# first_board5.net
KiCad netlist of a schematic drawn in EAGLE
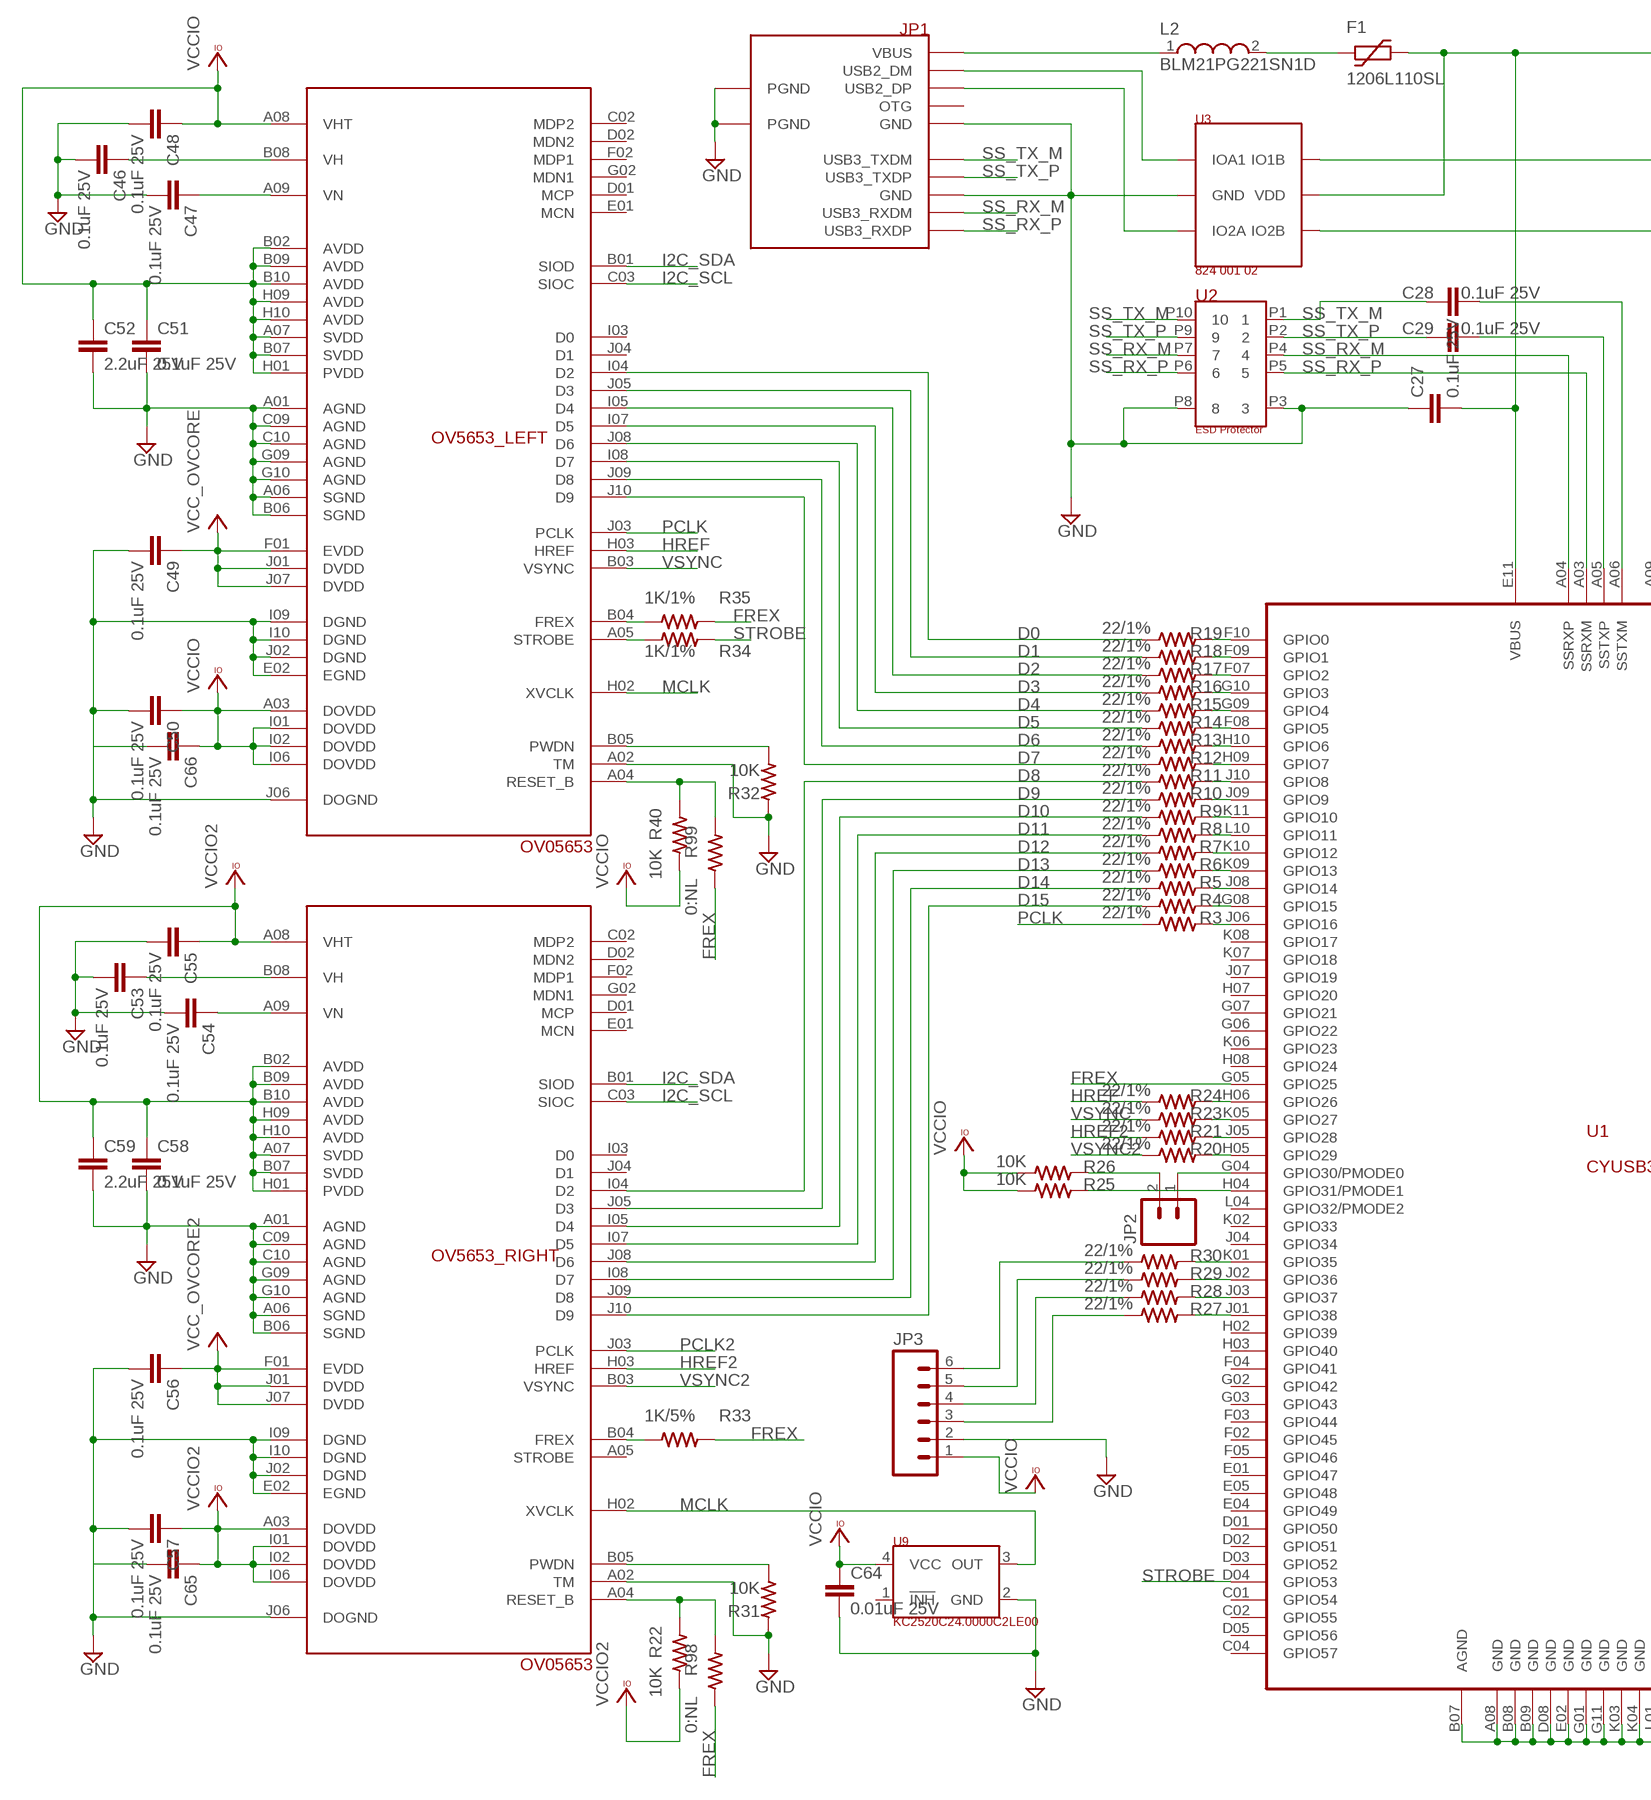
[diagram p0: schematic, sheet 1, part 1 of 2]
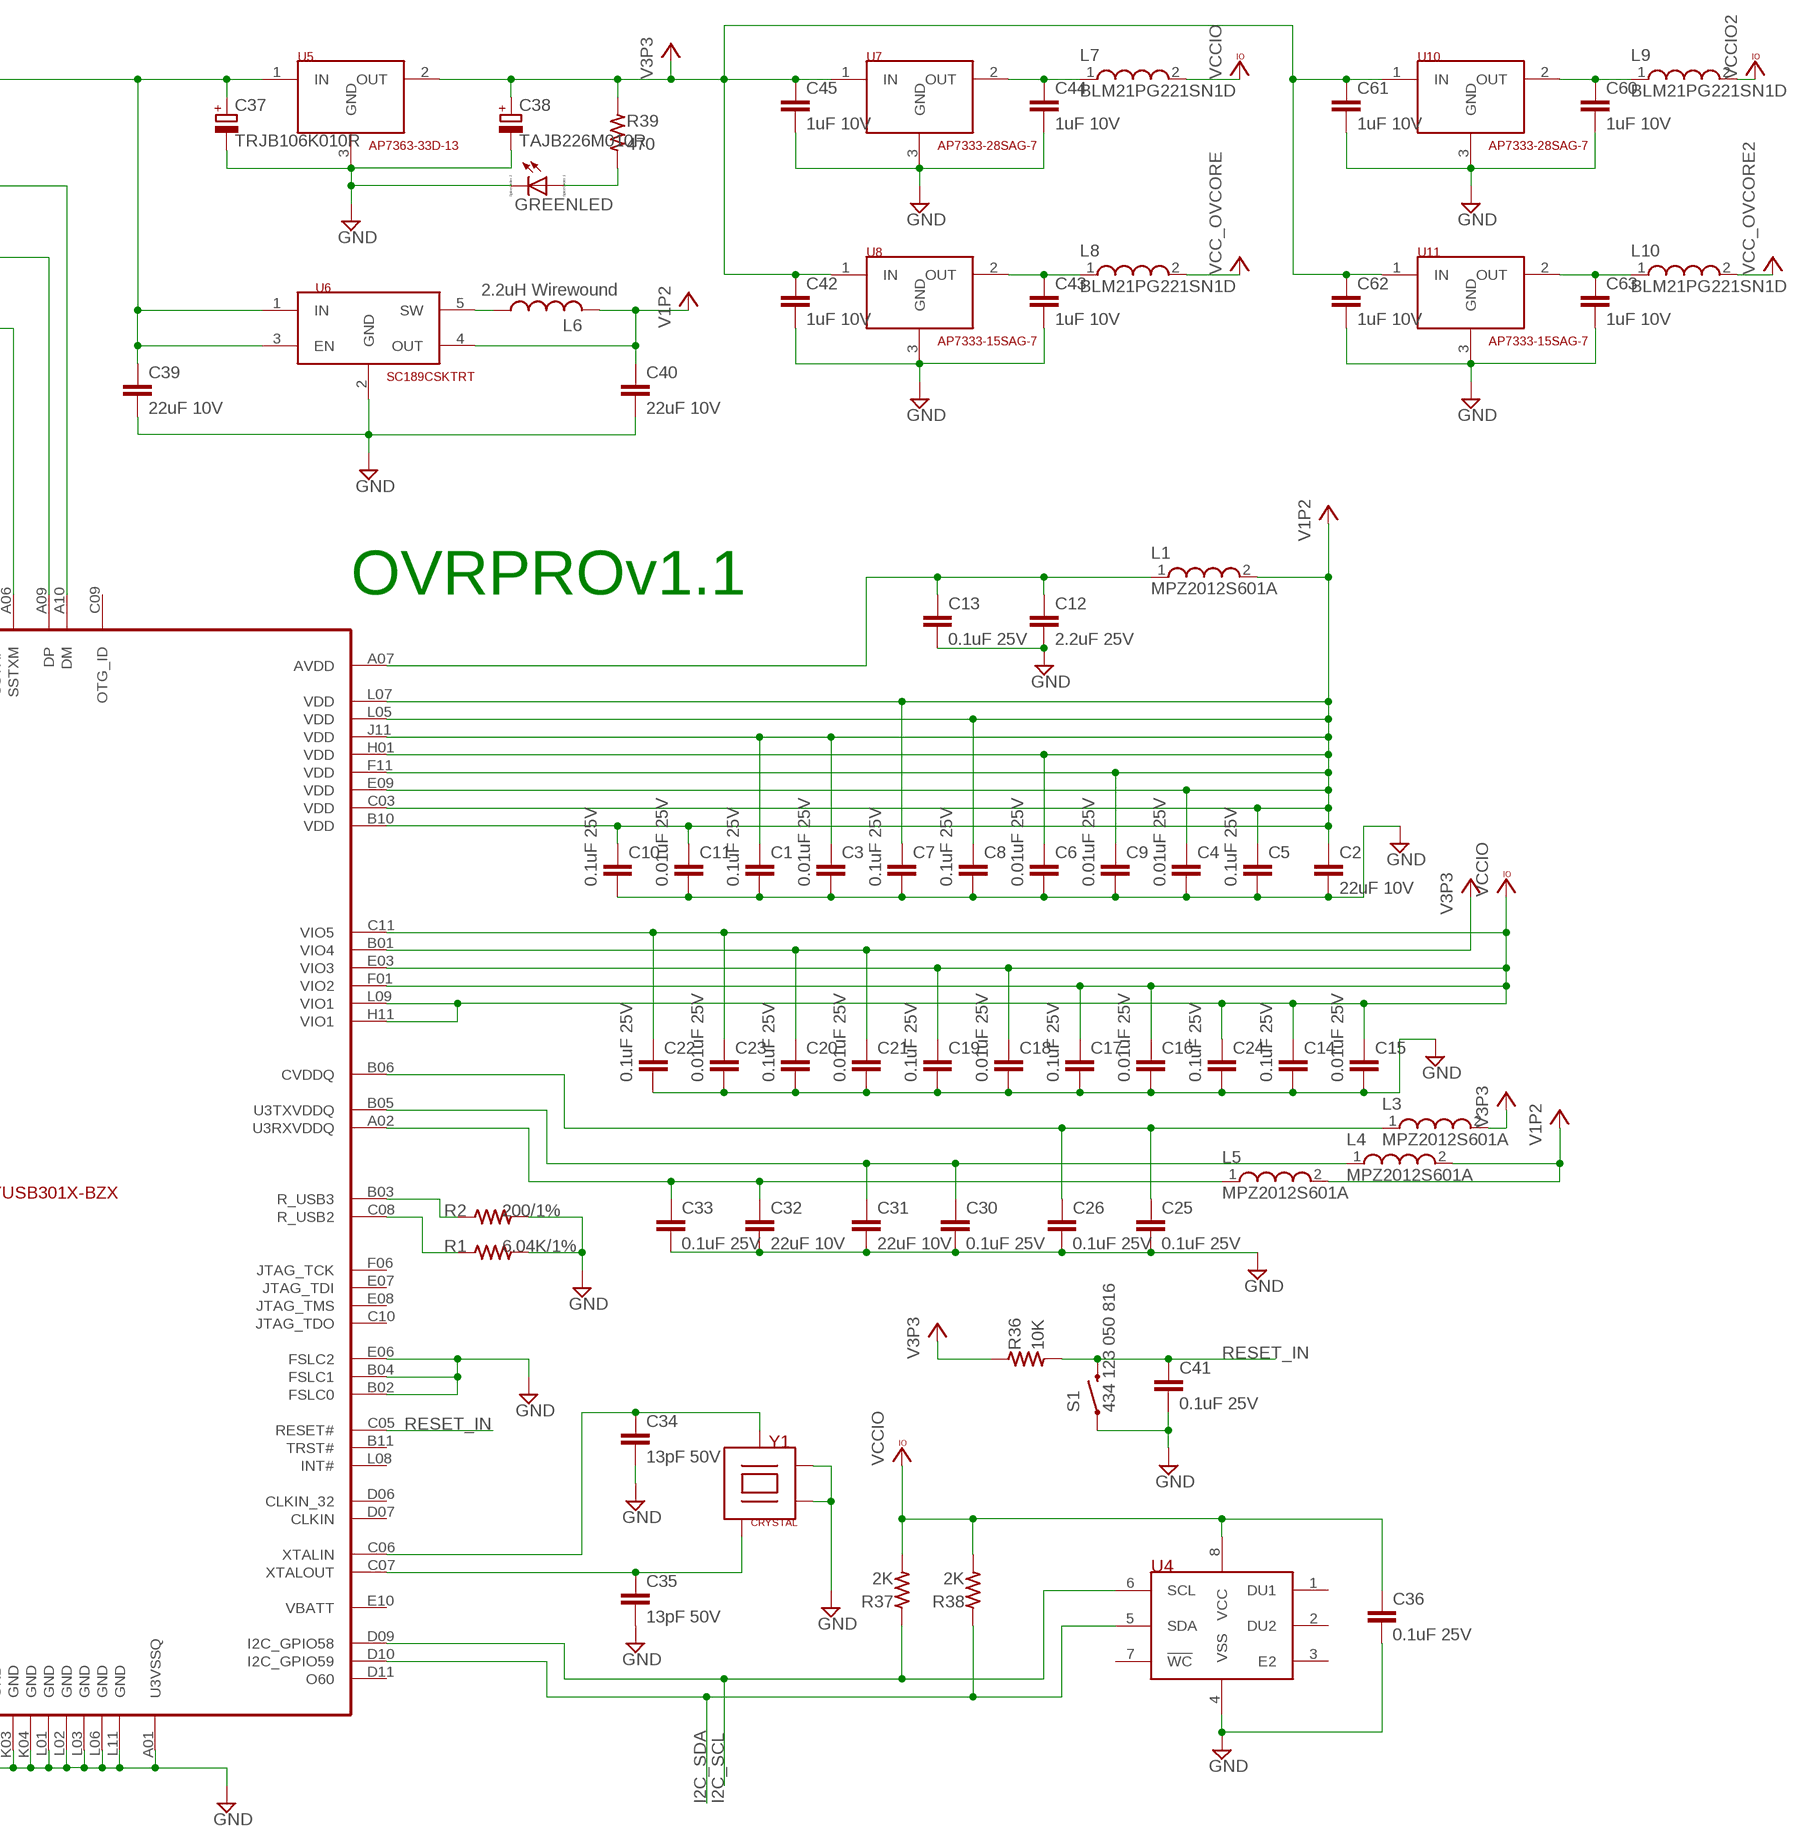
[diagram p1: schematic, sheet 1, part 2 of 2]

(export (version "E")
  (design (tool "Eeschema 10.0.6"))
  (components
    (comp (ref "C1")
      (value "0.1uF 25V")
      (footprint "eagle-import:C0402K")
      (libsource (lib "eagle-import") (part "C-EUC0402K"))
    )
    (comp (ref "C2")
      (value "22uF 10V")
      (footprint "eagle-import:C1206")
      (libsource (lib "eagle-import") (part "C-EUC1206"))
    )
    (comp (ref "C3")
      (value "0.01uF 25V")
      (footprint "eagle-import:C0402K")
      (libsource (lib "eagle-import") (part "C-EUC0402K"))
    )
    (comp (ref "C4")
      (value "0.01uF 25V")
      (footprint "eagle-import:C0402K")
      (libsource (lib "eagle-import") (part "C-EUC0402K"))
    )
    (comp (ref "C5")
      (value "0.1uF 25V")
      (footprint "eagle-import:C0402K")
      (libsource (lib "eagle-import") (part "C-EUC0402K"))
    )
    (comp (ref "C6")
      (value "0.01uF 25V")
      (footprint "eagle-import:C0402K")
      (libsource (lib "eagle-import") (part "C-EUC0402K"))
    )
    (comp (ref "C7")
      (value "0.1uF 25V")
      (footprint "eagle-import:C0402K")
      (libsource (lib "eagle-import") (part "C-EUC0402K"))
    )
    (comp (ref "C8")
      (value "0.1uF 25V")
      (footprint "eagle-import:C0402K")
      (libsource (lib "eagle-import") (part "C-EUC0402K"))
    )
    (comp (ref "C9")
      (value "0.01uF 25V")
      (footprint "eagle-import:C0402K")
      (libsource (lib "eagle-import") (part "C-EUC0402K"))
    )
    (comp (ref "C10")
      (value "0.1uF 25V")
      (footprint "eagle-import:C0402K")
      (libsource (lib "eagle-import") (part "C-EUC0402K"))
    )
    (comp (ref "C11")
      (value "0.01uF 25V")
      (footprint "eagle-import:C0402K")
      (libsource (lib "eagle-import") (part "C-EUC0402K"))
    )
    (comp (ref "C12")
      (value "2.2uF 25V")
      (footprint "eagle-import:C0805")
      (libsource (lib "eagle-import") (part "C-EUC0805"))
    )
    (comp (ref "C13")
      (value "0.1uF 25V")
      (footprint "eagle-import:C0402K")
      (libsource (lib "eagle-import") (part "C-EUC0402K"))
    )
    (comp (ref "C14")
      (value "0.1uF 25V")
      (footprint "eagle-import:C0402K")
      (libsource (lib "eagle-import") (part "C-EUC0402K"))
    )
    (comp (ref "C15")
      (value "0.01uF 25V")
      (footprint "eagle-import:C0402K")
      (libsource (lib "eagle-import") (part "C-EUC0402K"))
    )
    (comp (ref "C16")
      (value "0.01uF 25V")
      (footprint "eagle-import:C0402K")
      (libsource (lib "eagle-import") (part "C-EUC0402K"))
    )
    (comp (ref "C17")
      (value "0.1uF 25V")
      (footprint "eagle-import:C0402K")
      (libsource (lib "eagle-import") (part "C-EUC0402K"))
    )
    (comp (ref "C18")
      (value "0.01uF 25V")
      (footprint "eagle-import:C0402K")
      (libsource (lib "eagle-import") (part "C-EUC0402K"))
    )
    (comp (ref "C19")
      (value "0.1uF 25V")
      (footprint "eagle-import:C0402K")
      (libsource (lib "eagle-import") (part "C-EUC0402K"))
    )
    (comp (ref "C20")
      (value "0.1uF 25V")
      (footprint "eagle-import:C0402K")
      (libsource (lib "eagle-import") (part "C-EUC0402K"))
    )
    (comp (ref "C21")
      (value "0.01uF 25V")
      (footprint "eagle-import:C0402K")
      (libsource (lib "eagle-import") (part "C-EUC0402K"))
    )
    (comp (ref "C22")
      (value "0.1uF 25V")
      (footprint "eagle-import:C0402K")
      (libsource (lib "eagle-import") (part "C-EUC0402K"))
    )
    (comp (ref "C23")
      (value "0.01uF 25V")
      (footprint "eagle-import:C0402K")
      (libsource (lib "eagle-import") (part "C-EUC0402K"))
    )
    (comp (ref "C24")
      (value "0.1uF 25V")
      (footprint "eagle-import:C0402")
      (libsource (lib "eagle-import") (part "C-EUC0402"))
    )
    (comp (ref "C25")
      (value "0.1uF 25V")
      (footprint "eagle-import:C0402K")
      (libsource (lib "eagle-import") (part "C-EUC0402K"))
    )
    (comp (ref "C26")
      (value "0.1uF 25V")
      (footprint "eagle-import:C0402K")
      (libsource (lib "eagle-import") (part "C-EUC0402K"))
    )
    (comp (ref "C27")
      (value "0.1uF 25V")
      (footprint "eagle-import:C0402K")
      (libsource (lib "eagle-import") (part "C-EUC0402K"))
    )
    (comp (ref "C28")
      (value "0.1uF 25V")
      (footprint "eagle-import:C0402K")
      (libsource (lib "eagle-import") (part "C-EUC0402K"))
    )
    (comp (ref "C29")
      (value "0.1uF 25V")
      (footprint "eagle-import:C0402K")
      (libsource (lib "eagle-import") (part "C-EUC0402K"))
    )
    (comp (ref "C30")
      (value "0.1uF 25V")
      (footprint "eagle-import:C0402K")
      (libsource (lib "eagle-import") (part "C-EUC0402K"))
    )
    (comp (ref "C31")
      (value "22uF 10V")
      (footprint "eagle-import:C1206")
      (libsource (lib "eagle-import") (part "C-EUC1206"))
    )
    (comp (ref "C32")
      (value "22uF 10V")
      (footprint "eagle-import:C1206")
      (libsource (lib "eagle-import") (part "C-EUC1206"))
    )
    (comp (ref "C33")
      (value "0.1uF 25V")
      (footprint "eagle-import:C0402K")
      (libsource (lib "eagle-import") (part "C-EUC0402K"))
    )
    (comp (ref "C34")
      (value "13pF 50V")
      (footprint "eagle-import:C0402K")
      (libsource (lib "eagle-import") (part "C-EUC0402K"))
    )
    (comp (ref "C35")
      (value "13pF 50V")
      (footprint "eagle-import:C0402K")
      (libsource (lib "eagle-import") (part "C-EUC0402K"))
    )
    (comp (ref "C36")
      (value "0.1uF 25V")
      (footprint "eagle-import:C0402")
      (libsource (lib "eagle-import") (part "C-EUC0402"))
    )
    (comp (ref "C37")
      (value "TRJB106K010R")
      (footprint "eagle-import:CT3528")
      (libsource (lib "eagle-import") (part "CPOL-EUCT3528"))
    )
    (comp (ref "C38")
      (value "TAJB226M010R")
      (footprint "eagle-import:CT3528")
      (libsource (lib "eagle-import") (part "CPOL-EUCT3528"))
    )
    (comp (ref "C39")
      (value "22uF 10V")
      (footprint "eagle-import:C1206")
      (libsource (lib "eagle-import") (part "C-EUC1206"))
    )
    (comp (ref "C40")
      (value "22uF 10V")
      (footprint "eagle-import:C1206")
      (libsource (lib "eagle-import") (part "C-EUC1206"))
    )
    (comp (ref "C41")
      (value "0.1uF 25V")
      (footprint "eagle-import:C0402")
      (libsource (lib "eagle-import") (part "C-EUC0402"))
    )
    (comp (ref "C42")
      (value "1uF 10V")
      (footprint "eagle-import:C0402")
      (libsource (lib "eagle-import") (part "C-EUC0402"))
    )
    (comp (ref "C43")
      (value "1uF 10V")
      (footprint "eagle-import:C0402")
      (libsource (lib "eagle-import") (part "C-EUC0402"))
    )
    (comp (ref "C44")
      (value "1uF 10V")
      (footprint "eagle-import:C0402")
      (libsource (lib "eagle-import") (part "C-EUC0402"))
    )
    (comp (ref "C45")
      (value "1uF 10V")
      (footprint "eagle-import:C0402")
      (libsource (lib "eagle-import") (part "C-EUC0402"))
    )
    (comp (ref "C46")
      (value "0.1uF 25V")
      (footprint "eagle-import:C0402K")
      (libsource (lib "eagle-import") (part "C-EUC0402K"))
    )
    (comp (ref "C47")
      (value "0.1uF 25V")
      (footprint "eagle-import:C0402K")
      (libsource (lib "eagle-import") (part "C-EUC0402K"))
    )
    (comp (ref "C48")
      (value "0.1uF 25V")
      (footprint "eagle-import:C0402K")
      (libsource (lib "eagle-import") (part "C-EUC0402K"))
    )
    (comp (ref "C49")
      (value "0.1uF 25V")
      (footprint "eagle-import:C0402K")
      (libsource (lib "eagle-import") (part "C-EUC0402K"))
    )
    (comp (ref "C50")
      (value "0.1uF 25V")
      (footprint "eagle-import:C0402K")
      (libsource (lib "eagle-import") (part "C-EUC0402K"))
    )
    (comp (ref "C51")
      (value "0.1uF 25V")
      (footprint "eagle-import:C0402K")
      (libsource (lib "eagle-import") (part "C-EUC0402K"))
    )
    (comp (ref "C52")
      (value "2.2uF 25V")
      (footprint "eagle-import:C0805")
      (libsource (lib "eagle-import") (part "C-EUC0805"))
    )
    (comp (ref "C53")
      (value "0.1uF 25V")
      (footprint "eagle-import:C0402K")
      (libsource (lib "eagle-import") (part "C-EUC0402K"))
    )
    (comp (ref "C54")
      (value "0.1uF 25V")
      (footprint "eagle-import:C0402K")
      (libsource (lib "eagle-import") (part "C-EUC0402K"))
    )
    (comp (ref "C55")
      (value "0.1uF 25V")
      (footprint "eagle-import:C0402K")
      (libsource (lib "eagle-import") (part "C-EUC0402K"))
    )
    (comp (ref "C56")
      (value "0.1uF 25V")
      (footprint "eagle-import:C0402K")
      (libsource (lib "eagle-import") (part "C-EUC0402K"))
    )
    (comp (ref "C57")
      (value "0.1uF 25V")
      (footprint "eagle-import:C0402K")
      (libsource (lib "eagle-import") (part "C-EUC0402K"))
    )
    (comp (ref "C58")
      (value "0.1uF 25V")
      (footprint "eagle-import:C0402K")
      (libsource (lib "eagle-import") (part "C-EUC0402K"))
    )
    (comp (ref "C59")
      (value "2.2uF 25V")
      (footprint "eagle-import:C0805")
      (libsource (lib "eagle-import") (part "C-EUC0805"))
    )
    (comp (ref "C60")
      (value "1uF 10V")
      (footprint "eagle-import:C0402")
      (libsource (lib "eagle-import") (part "C-EUC0402"))
    )
    (comp (ref "C61")
      (value "1uF 10V")
      (footprint "eagle-import:C0402")
      (libsource (lib "eagle-import") (part "C-EUC0402"))
    )
    (comp (ref "C62")
      (value "1uF 10V")
      (footprint "eagle-import:C0402")
      (libsource (lib "eagle-import") (part "C-EUC0402"))
    )
    (comp (ref "C63")
      (value "1uF 10V")
      (footprint "eagle-import:C0402")
      (libsource (lib "eagle-import") (part "C-EUC0402"))
    )
    (comp (ref "C64")
      (value "0.01uF 25V")
      (footprint "eagle-import:C0402K")
      (libsource (lib "eagle-import") (part "C-EUC0402K"))
    )
    (comp (ref "C65")
      (value "0.1uF 25V")
      (footprint "eagle-import:C0402K")
      (libsource (lib "eagle-import") (part "C-EUC0402K"))
    )
    (comp (ref "C66")
      (value "0.1uF 25V")
      (footprint "eagle-import:C0402K")
      (libsource (lib "eagle-import") (part "C-EUC0402K"))
    )
    (comp (ref "F1")
      (value "1206L110SL")
      (footprint "eagle-import:1206L")
      (libsource (lib "eagle-import") (part "1206L"))
    )
    (comp (ref "GREENLED")
      (value "LED_ESML0603")
      (footprint "eagle-import:LED_SML0603")
      (libsource (lib "eagle-import") (part "LED_ESML0603"))
    )
    (comp (ref "JP1")
      (value "ZX360D-B-10PUSB3")
      (footprint "eagle-import:ZX360D-B-10PUSB3")
      (libsource (lib "eagle-import") (part "ZX360D-B-10PUSB3"))
    )
    (comp (ref "JP2")
      (value "M02PTH")
      (footprint "eagle-import:1X02")
      (libsource (lib "eagle-import") (part "M02PTH"))
    )
    (comp (ref "JP3")
      (value "M06SILK_FEMALE_PTH")
      (footprint "eagle-import:1X06")
      (libsource (lib "eagle-import") (part "M06SILK_FEMALE_PTH"))
    )
    (comp (ref "L1")
      (value "MPZ2012S601A")
      (footprint "eagle-import:WE-CBA_0805(W=3)")
      (libsource (lib "eagle-import") (part "WE-CBA_0805(WB/HS)"))
    )
    (comp (ref "L2")
      (value "BLM21PG221SN1D")
      (footprint "eagle-import:WE-CBA_0805(W=3)")
      (libsource (lib "eagle-import") (part "WE-CBA_0805(WB/HS)"))
    )
    (comp (ref "L3")
      (value "MPZ2012S601A")
      (footprint "eagle-import:WE-CBA_0805(W=3)")
      (libsource (lib "eagle-import") (part "WE-CBA_0805(WB/HS)"))
    )
    (comp (ref "L4")
      (value "MPZ2012S601A")
      (footprint "eagle-import:WE-CBA_0805(W=3)")
      (libsource (lib "eagle-import") (part "WE-CBA_0805(WB/HS)"))
    )
    (comp (ref "L5")
      (value "MPZ2012S601A")
      (footprint "eagle-import:WE-CBA_0805(W=3)")
      (libsource (lib "eagle-import") (part "WE-CBA_0805(WB/HS)"))
    )
    (comp (ref "L6")
      (value "2.2uH Wirewound")
      (footprint "eagle-import:L3225M")
      (libsource (lib "eagle-import") (part "L-USL3225M"))
    )
    (comp (ref "L7")
      (value "BLM21PG221SN1D")
      (footprint "eagle-import:WE-CBA_0805(W=3)")
      (libsource (lib "eagle-import") (part "WE-CBA_0805(WB/HS)"))
    )
    (comp (ref "L8")
      (value "BLM21PG221SN1D")
      (footprint "eagle-import:WE-CBA_0805(W=3)")
      (libsource (lib "eagle-import") (part "WE-CBA_0805(WB/HS)"))
    )
    (comp (ref "L9")
      (value "BLM21PG221SN1D")
      (footprint "eagle-import:WE-CBA_0805(W=3)")
      (libsource (lib "eagle-import") (part "WE-CBA_0805(WB/HS)"))
    )
    (comp (ref "L10")
      (value "BLM21PG221SN1D")
      (footprint "eagle-import:WE-CBA_0805(W=3)")
      (libsource (lib "eagle-import") (part "WE-CBA_0805(WB/HS)"))
    )
    (comp (ref "OV5653_LEFT")
      (value "OV05653-A66A")
      (footprint "eagle-import:OV05653-A66A")
      (libsource (lib "eagle-import") (part "OV05653-A66A"))
    )
    (comp (ref "OV5653_RIGHT")
      (value "OV05653-A66A")
      (footprint "eagle-import:OV05653-A66A")
      (libsource (lib "eagle-import") (part "OV05653-A66A"))
    )
    (comp (ref "R1")
      (value "6.04K/1%")
      (footprint "eagle-import:SMD1608")
      (libsource (lib "eagle-import") (part "RESISTOR-US1608"))
    )
    (comp (ref "R2")
      (value "200/1%")
      (footprint "eagle-import:SMD1608")
      (libsource (lib "eagle-import") (part "RESISTOR-US1608"))
    )
    (comp (ref "R3")
      (value "22/1%")
      (footprint "eagle-import:SMD1005")
      (libsource (lib "eagle-import") (part "RESISTOR-US1005"))
    )
    (comp (ref "R4")
      (value "22/1%")
      (footprint "eagle-import:SMD1005")
      (libsource (lib "eagle-import") (part "RESISTOR-US1005"))
    )
    (comp (ref "R5")
      (value "22/1%")
      (footprint "eagle-import:SMD1005")
      (libsource (lib "eagle-import") (part "RESISTOR-US1005"))
    )
    (comp (ref "R6")
      (value "22/1%")
      (footprint "eagle-import:SMD1005")
      (libsource (lib "eagle-import") (part "RESISTOR-US1005"))
    )
    (comp (ref "R7")
      (value "22/1%")
      (footprint "eagle-import:SMD1005")
      (libsource (lib "eagle-import") (part "RESISTOR-US1005"))
    )
    (comp (ref "R8")
      (value "22/1%")
      (footprint "eagle-import:SMD1005")
      (libsource (lib "eagle-import") (part "RESISTOR-US1005"))
    )
    (comp (ref "R9")
      (value "22/1%")
      (footprint "eagle-import:SMD1005")
      (libsource (lib "eagle-import") (part "RESISTOR-US1005"))
    )
    (comp (ref "R10")
      (value "22/1%")
      (footprint "eagle-import:SMD1005")
      (libsource (lib "eagle-import") (part "RESISTOR-US1005"))
    )
    (comp (ref "R11")
      (value "22/1%")
      (footprint "eagle-import:SMD1005")
      (libsource (lib "eagle-import") (part "RESISTOR-US1005"))
    )
    (comp (ref "R12")
      (value "22/1%")
      (footprint "eagle-import:SMD1005")
      (libsource (lib "eagle-import") (part "RESISTOR-US1005"))
    )
    (comp (ref "R13")
      (value "22/1%")
      (footprint "eagle-import:SMD1005")
      (libsource (lib "eagle-import") (part "RESISTOR-US1005"))
    )
    (comp (ref "R14")
      (value "22/1%")
      (footprint "eagle-import:SMD1005")
      (libsource (lib "eagle-import") (part "RESISTOR-US1005"))
    )
    (comp (ref "R15")
      (value "22/1%")
      (footprint "eagle-import:SMD1005")
      (libsource (lib "eagle-import") (part "RESISTOR-US1005"))
    )
    (comp (ref "R16")
      (value "22/1%")
      (footprint "eagle-import:SMD1005")
      (libsource (lib "eagle-import") (part "RESISTOR-US1005"))
    )
    (comp (ref "R17")
      (value "22/1%")
      (footprint "eagle-import:SMD1005")
      (libsource (lib "eagle-import") (part "RESISTOR-US1005"))
    )
    (comp (ref "R18")
      (value "22/1%")
      (footprint "eagle-import:SMD1005")
      (libsource (lib "eagle-import") (part "RESISTOR-US1005"))
    )
    (comp (ref "R19")
      (value "22/1%")
      (footprint "eagle-import:SMD1005")
      (libsource (lib "eagle-import") (part "RESISTOR-US1005"))
    )
    (comp (ref "R20")
      (value "22/1%")
      (footprint "eagle-import:SMD1005")
      (libsource (lib "eagle-import") (part "RESISTOR-US1005"))
    )
    (comp (ref "R21")
      (value "22/1%")
      (footprint "eagle-import:SMD1005")
      (libsource (lib "eagle-import") (part "RESISTOR-US1005"))
    )
    (comp (ref "R22")
      (value "10K")
      (footprint "eagle-import:SMD1608")
      (libsource (lib "eagle-import") (part "RESISTOR-US1608"))
    )
    (comp (ref "R23")
      (value "22/1%")
      (footprint "eagle-import:SMD1005")
      (libsource (lib "eagle-import") (part "RESISTOR-US1005"))
    )
    (comp (ref "R24")
      (value "22/1%")
      (footprint "eagle-import:SMD1005")
      (libsource (lib "eagle-import") (part "RESISTOR-US1005"))
    )
    (comp (ref "R25")
      (value "10K")
      (footprint "eagle-import:SMD1608")
      (libsource (lib "eagle-import") (part "RESISTOR-US1608"))
    )
    (comp (ref "R26")
      (value "10K")
      (footprint "eagle-import:SMD1608")
      (libsource (lib "eagle-import") (part "RESISTOR-US1608"))
    )
    (comp (ref "R27")
      (value "22/1%")
      (footprint "eagle-import:SMD1005")
      (libsource (lib "eagle-import") (part "RESISTOR-US1005"))
    )
    (comp (ref "R28")
      (value "22/1%")
      (footprint "eagle-import:SMD1005")
      (libsource (lib "eagle-import") (part "RESISTOR-US1005"))
    )
    (comp (ref "R29")
      (value "22/1%")
      (footprint "eagle-import:SMD1005")
      (libsource (lib "eagle-import") (part "RESISTOR-US1005"))
    )
    (comp (ref "R30")
      (value "22/1%")
      (footprint "eagle-import:SMD1005")
      (libsource (lib "eagle-import") (part "RESISTOR-US1005"))
    )
    (comp (ref "R31")
      (value "10K")
      (footprint "eagle-import:SMD1608")
      (libsource (lib "eagle-import") (part "RESISTOR-US1608"))
    )
    (comp (ref "R32")
      (value "10K")
      (footprint "eagle-import:SMD1608")
      (libsource (lib "eagle-import") (part "RESISTOR-US1608"))
    )
    (comp (ref "R33")
      (value "1K/5%")
      (footprint "eagle-import:SMD1005")
      (libsource (lib "eagle-import") (part "RESISTOR-US1005"))
    )
    (comp (ref "R34")
      (value "1K/1%")
      (footprint "eagle-import:SMD1005")
      (libsource (lib "eagle-import") (part "RESISTOR-US1005"))
    )
    (comp (ref "R35")
      (value "1K/1%")
      (footprint "eagle-import:SMD1005")
      (libsource (lib "eagle-import") (part "RESISTOR-US1005"))
    )
    (comp (ref "R36")
      (value "10K")
      (footprint "eagle-import:SMD1608")
      (libsource (lib "eagle-import") (part "RESISTOR-US1608"))
    )
    (comp (ref "R37")
      (value "2K")
      (footprint "eagle-import:SMD1608")
      (libsource (lib "eagle-import") (part "RESISTOR-US1608"))
    )
    (comp (ref "R38")
      (value "2K")
      (footprint "eagle-import:SMD1608")
      (libsource (lib "eagle-import") (part "RESISTOR-US1608"))
    )
    (comp (ref "R39")
      (value "470")
      (footprint "eagle-import:SMD1608")
      (libsource (lib "eagle-import") (part "RESISTOR-US1608"))
    )
    (comp (ref "R40")
      (value "10K")
      (footprint "eagle-import:SMD1608")
      (libsource (lib "eagle-import") (part "RESISTOR-US1608"))
    )
    (comp (ref "R98")
      (value "0:NL")
      (footprint "eagle-import:SMD1005")
      (libsource (lib "eagle-import") (part "RESISTOR-US1005"))
    )
    (comp (ref "R99")
      (value "0:NL")
      (footprint "eagle-import:SMD1005")
      (libsource (lib "eagle-import") (part "RESISTOR-US1005"))
    )
    (comp (ref "S1")
      (value "434 123 050 816")
      (footprint "eagle-import:TACTILE-SWITCH-1101NE")
      (libsource (lib "eagle-import") (part "SWITCH-MOMENTARY-2SMD-1101NE"))
    )
    (comp (ref "U1")
      (value "CYUSB301X-BZX")
      (footprint "eagle-import:BGA121")
      (libsource (lib "eagle-import") (part "CYUSB301X-BZX"))
    )
    (comp (ref "U2")
      (value "SP3010-04UTG")
      (footprint "eagle-import:SP3010-04UTG")
      (libsource (lib "eagle-import") (part "SP3010-04UTG"))
    )
    (comp (ref "U3")
      (value "WE-82400102")
      (footprint "eagle-import:WE-82400102")
      (libsource (lib "eagle-import") (part "WE-82400102"))
    )
    (comp (ref "U4")
      (value "M24M02-DRMN6TP")
      (footprint "eagle-import:SO-08")
      (libsource (lib "eagle-import") (part "M24M02-DRMN6TP"))
    )
    (comp (ref "U5")
      (value "AP7363-33D-13")
      (footprint "eagle-import:TO-252")
      (libsource (lib "eagle-import") (part "AP7363-XXD-13"))
    )
    (comp (ref "U6")
      (value "SC189CSKTRT")
      (footprint "eagle-import:SOT23-5")
      (libsource (lib "eagle-import") (part "PAM2305AABXXX"))
    )
    (comp (ref "U7")
      (value "AP7333-28SAG-7")
      (footprint "eagle-import:SOT23")
      (libsource (lib "eagle-import") (part "AP7333-XXSAG-7"))
    )
    (comp (ref "U8")
      (value "AP7333-15SAG-7")
      (footprint "eagle-import:SOT23")
      (libsource (lib "eagle-import") (part "AP7333-XXSAG-7"))
    )
    (comp (ref "U9")
      (value "KC2520C24.0000C2LE00")
      (footprint "eagle-import:KC2520C-C2")
      (libsource (lib "eagle-import") (part "KC2520C-C2"))
    )
    (comp (ref "U10")
      (value "AP7333-28SAG-7")
      (footprint "eagle-import:SOT23")
      (libsource (lib "eagle-import") (part "AP7333-XXSAG-7"))
    )
    (comp (ref "U11")
      (value "AP7333-15SAG-7")
      (footprint "eagle-import:SOT23")
      (libsource (lib "eagle-import") (part "AP7333-XXSAG-7"))
    )
    (comp (ref "Y1")
      (value "NX2520SACRY")
      (footprint "eagle-import:NX2520SACRY")
      (libsource (lib "eagle-import") (part "NX2520SACRY"))
    )
  )
  (nets
    (net (code "1") (name "+3V3") (class "Default")
      (node (ref "C20") (pin "1") (pinfunction "1_1") (pintype "passive"))
      (node (ref "C21") (pin "1") (pinfunction "1_1") (pintype "passive"))
      (node (ref "C38") (pin "+") (pinfunction "+_+") (pintype "passive"))
      (node (ref "C42") (pin "1") (pinfunction "1_1") (pintype "passive"))
      (node (ref "C45") (pin "1") (pinfunction "1_1") (pintype "passive"))
      (node (ref "C61") (pin "1") (pinfunction "1_1") (pintype "passive"))
      (node (ref "C62") (pin "1") (pinfunction "1_1") (pintype "passive"))
      (node (ref "L3") (pin "2") (pinfunction "2_2") (pintype "passive"))
      (node (ref "R36") (pin "1") (pinfunction "1_1") (pintype "passive"))
      (node (ref "R39") (pin "1") (pinfunction "1_1") (pintype "passive"))
      (node (ref "U1") (pin "B01") (pinfunction "VIO4_B01") (pintype "power_in"))
      (node (ref "U10") (pin "1") (pinfunction "IN_1") (pintype "power_in"))
      (node (ref "U11") (pin "1") (pinfunction "IN_1") (pintype "power_in"))
      (node (ref "U5") (pin "2") (pinfunction "OUT_2") (pintype "power_in"))
      (node (ref "U7") (pin "1") (pinfunction "IN_1") (pintype "power_in"))
      (node (ref "U8") (pin "1") (pinfunction "IN_1") (pintype "power_in"))
    )
    (net (code "2") (name "+5V") (class "Default")
      (node (ref "C1") (pin "1") (pinfunction "1_1") (pintype "passive"))
      (node (ref "C10") (pin "1") (pinfunction "1_1") (pintype "passive"))
      (node (ref "C11") (pin "1") (pinfunction "1_1") (pintype "passive"))
      (node (ref "C2") (pin "1") (pinfunction "1_1") (pintype "passive"))
      (node (ref "C3") (pin "1") (pinfunction "1_1") (pintype "passive"))
      (node (ref "C4") (pin "1") (pinfunction "1_1") (pintype "passive"))
      (node (ref "C40") (pin "1") (pinfunction "1_1") (pintype "passive"))
      (node (ref "C5") (pin "1") (pinfunction "1_1") (pintype "passive"))
      (node (ref "C6") (pin "1") (pinfunction "1_1") (pintype "passive"))
      (node (ref "C7") (pin "1") (pinfunction "1_1") (pintype "passive"))
      (node (ref "C8") (pin "1") (pinfunction "1_1") (pintype "passive"))
      (node (ref "C9") (pin "1") (pinfunction "1_1") (pintype "passive"))
      (node (ref "L1") (pin "2") (pinfunction "2_2") (pintype "passive"))
      (node (ref "L4") (pin "2") (pinfunction "2_2") (pintype "passive"))
      (node (ref "L5") (pin "2") (pinfunction "2_2") (pintype "passive"))
      (node (ref "L6") (pin "2") (pinfunction "2_2") (pintype "passive"))
      (node (ref "U1") (pin "B10") (pinfunction "VDD_B10") (pintype "power_in"))
      (node (ref "U1") (pin "C03") (pinfunction "VDD_C03") (pintype "power_in"))
      (node (ref "U1") (pin "E09") (pinfunction "VDD_E09") (pintype "power_in"))
      (node (ref "U1") (pin "F11") (pinfunction "VDD_F11") (pintype "power_in"))
      (node (ref "U1") (pin "H01") (pinfunction "VDD_H01") (pintype "power_in"))
      (node (ref "U1") (pin "J11") (pinfunction "VDD_J11") (pintype "power_in"))
      (node (ref "U1") (pin "L05") (pinfunction "VDD_L05") (pintype "power_in"))
      (node (ref "U1") (pin "L07") (pinfunction "VDD_L07") (pintype "power_in"))
      (node (ref "U6") (pin "4") (pinfunction "OUT_4") (pintype "power_in"))
    )
    (net (code "3") (name "D0") (class "Default")
      (node (ref "OV5653_LEFT") (pin "I04") (pinfunction "D2_I04") (pintype "bidirectional"))
      (node (ref "R19") (pin "1") (pinfunction "1_1") (pintype "passive"))
    )
    (net (code "4") (name "D1") (class "Default")
      (node (ref "OV5653_LEFT") (pin "J05") (pinfunction "D3_J05") (pintype "bidirectional"))
      (node (ref "R18") (pin "1") (pinfunction "1_1") (pintype "passive"))
    )
    (net (code "5") (name "D2") (class "Default")
      (node (ref "OV5653_LEFT") (pin "I05") (pinfunction "D4_I05") (pintype "bidirectional"))
      (node (ref "R17") (pin "1") (pinfunction "1_1") (pintype "passive"))
    )
    (net (code "6") (name "D3") (class "Default")
      (node (ref "OV5653_LEFT") (pin "I07") (pinfunction "D5_I07") (pintype "bidirectional"))
      (node (ref "R16") (pin "1") (pinfunction "1_1") (pintype "passive"))
    )
    (net (code "7") (name "D4") (class "Default")
      (node (ref "OV5653_LEFT") (pin "J08") (pinfunction "D6_J08") (pintype "bidirectional"))
      (node (ref "R15") (pin "1") (pinfunction "1_1") (pintype "passive"))
    )
    (net (code "8") (name "D5") (class "Default")
      (node (ref "OV5653_LEFT") (pin "I08") (pinfunction "D7_I08") (pintype "bidirectional"))
      (node (ref "R14") (pin "1") (pinfunction "1_1") (pintype "passive"))
    )
    (net (code "9") (name "D6") (class "Default")
      (node (ref "OV5653_LEFT") (pin "J09") (pinfunction "D8_J09") (pintype "bidirectional"))
      (node (ref "R13") (pin "1") (pinfunction "1_1") (pintype "passive"))
    )
    (net (code "10") (name "D7") (class "Default")
      (node (ref "OV5653_LEFT") (pin "J10") (pinfunction "D9_J10") (pintype "bidirectional"))
      (node (ref "R12") (pin "1") (pinfunction "1_1") (pintype "passive"))
    )
    (net (code "11") (name "D8") (class "Default")
      (node (ref "OV5653_RIGHT") (pin "I04") (pinfunction "D2_I04") (pintype "bidirectional"))
      (node (ref "R11") (pin "1") (pinfunction "1_1") (pintype "passive"))
    )
    (net (code "12") (name "D9") (class "Default")
      (node (ref "OV5653_RIGHT") (pin "J05") (pinfunction "D3_J05") (pintype "bidirectional"))
      (node (ref "R10") (pin "1") (pinfunction "1_1") (pintype "passive"))
    )
    (net (code "13") (name "D10") (class "Default")
      (node (ref "OV5653_RIGHT") (pin "I05") (pinfunction "D4_I05") (pintype "bidirectional"))
      (node (ref "R9") (pin "1") (pinfunction "1_1") (pintype "passive"))
    )
    (net (code "14") (name "D11") (class "Default")
      (node (ref "OV5653_RIGHT") (pin "I07") (pinfunction "D5_I07") (pintype "bidirectional"))
      (node (ref "R8") (pin "1") (pinfunction "1_1") (pintype "passive"))
    )
    (net (code "15") (name "D12") (class "Default")
      (node (ref "OV5653_RIGHT") (pin "J08") (pinfunction "D6_J08") (pintype "bidirectional"))
      (node (ref "R7") (pin "1") (pinfunction "1_1") (pintype "passive"))
    )
    (net (code "16") (name "D13") (class "Default")
      (node (ref "OV5653_RIGHT") (pin "I08") (pinfunction "D7_I08") (pintype "bidirectional"))
      (node (ref "R6") (pin "1") (pinfunction "1_1") (pintype "passive"))
    )
    (net (code "17") (name "D14") (class "Default")
      (node (ref "OV5653_RIGHT") (pin "J09") (pinfunction "D8_J09") (pintype "bidirectional"))
      (node (ref "R5") (pin "1") (pinfunction "1_1") (pintype "passive"))
    )
    (net (code "18") (name "D15") (class "Default")
      (node (ref "OV5653_RIGHT") (pin "J10") (pinfunction "D9_J10") (pintype "bidirectional"))
      (node (ref "R4") (pin "1") (pinfunction "1_1") (pintype "passive"))
    )
    (net (code "19") (name "FREX") (class "Default")
      (node (ref "R33") (pin "2") (pinfunction "2_2") (pintype "passive"))
      (node (ref "R35") (pin "2") (pinfunction "2_2") (pintype "passive"))
      (node (ref "R98") (pin "1") (pinfunction "1_1") (pintype "passive"))
      (node (ref "R99") (pin "1") (pinfunction "1_1") (pintype "passive"))
      (node (ref "U1") (pin "G05") (pinfunction "GPIO25_G05") (pintype "bidirectional"))
    )
    (net (code "20") (name "GND") (class "Default")
      (node (ref "C1") (pin "2") (pinfunction "2_2") (pintype "passive"))
      (node (ref "C10") (pin "2") (pinfunction "2_2") (pintype "passive"))
      (node (ref "C11") (pin "2") (pinfunction "2_2") (pintype "passive"))
      (node (ref "C12") (pin "2") (pinfunction "2_2") (pintype "passive"))
      (node (ref "C13") (pin "2") (pinfunction "2_2") (pintype "passive"))
      (node (ref "C14") (pin "2") (pinfunction "2_2") (pintype "passive"))
      (node (ref "C15") (pin "2") (pinfunction "2_2") (pintype "passive"))
      (node (ref "C16") (pin "2") (pinfunction "2_2") (pintype "passive"))
      (node (ref "C17") (pin "2") (pinfunction "2_2") (pintype "passive"))
      (node (ref "C18") (pin "2") (pinfunction "2_2") (pintype "passive"))
      (node (ref "C19") (pin "2") (pinfunction "2_2") (pintype "passive"))
      (node (ref "C2") (pin "2") (pinfunction "2_2") (pintype "passive"))
      (node (ref "C20") (pin "2") (pinfunction "2_2") (pintype "passive"))
      (node (ref "C21") (pin "2") (pinfunction "2_2") (pintype "passive"))
      (node (ref "C22") (pin "2") (pinfunction "2_2") (pintype "passive"))
      (node (ref "C23") (pin "2") (pinfunction "2_2") (pintype "passive"))
      (node (ref "C24") (pin "2") (pinfunction "2_2") (pintype "passive"))
      (node (ref "C25") (pin "2") (pinfunction "2_2") (pintype "passive"))
      (node (ref "C26") (pin "2") (pinfunction "2_2") (pintype "passive"))
      (node (ref "C27") (pin "1") (pinfunction "1_1") (pintype "passive"))
      (node (ref "C3") (pin "2") (pinfunction "2_2") (pintype "passive"))
      (node (ref "C30") (pin "2") (pinfunction "2_2") (pintype "passive"))
      (node (ref "C31") (pin "2") (pinfunction "2_2") (pintype "passive"))
      (node (ref "C32") (pin "2") (pinfunction "2_2") (pintype "passive"))
      (node (ref "C33") (pin "2") (pinfunction "2_2") (pintype "passive"))
      (node (ref "C34") (pin "2") (pinfunction "2_2") (pintype "passive"))
      (node (ref "C35") (pin "2") (pinfunction "2_2") (pintype "passive"))
      (node (ref "C36") (pin "2") (pinfunction "2_2") (pintype "passive"))
      (node (ref "C37") (pin "-") (pinfunction "-_-") (pintype "passive"))
      (node (ref "C38") (pin "-") (pinfunction "-_-") (pintype "passive"))
      (node (ref "C39") (pin "2") (pinfunction "2_2") (pintype "passive"))
      (node (ref "C4") (pin "2") (pinfunction "2_2") (pintype "passive"))
      (node (ref "C40") (pin "2") (pinfunction "2_2") (pintype "passive"))
      (node (ref "C41") (pin "2") (pinfunction "2_2") (pintype "passive"))
      (node (ref "C42") (pin "2") (pinfunction "2_2") (pintype "passive"))
      (node (ref "C43") (pin "2") (pinfunction "2_2") (pintype "passive"))
      (node (ref "C44") (pin "2") (pinfunction "2_2") (pintype "passive"))
      (node (ref "C45") (pin "2") (pinfunction "2_2") (pintype "passive"))
      (node (ref "C46") (pin "2") (pinfunction "2_2") (pintype "passive"))
      (node (ref "C47") (pin "2") (pinfunction "2_2") (pintype "passive"))
      (node (ref "C48") (pin "2") (pinfunction "2_2") (pintype "passive"))
      (node (ref "C49") (pin "2") (pinfunction "2_2") (pintype "passive"))
      (node (ref "C5") (pin "2") (pinfunction "2_2") (pintype "passive"))
      (node (ref "C50") (pin "2") (pinfunction "2_2") (pintype "passive"))
      (node (ref "C51") (pin "2") (pinfunction "2_2") (pintype "passive"))
      (node (ref "C52") (pin "2") (pinfunction "2_2") (pintype "passive"))
      (node (ref "C53") (pin "2") (pinfunction "2_2") (pintype "passive"))
      (node (ref "C54") (pin "2") (pinfunction "2_2") (pintype "passive"))
      (node (ref "C55") (pin "2") (pinfunction "2_2") (pintype "passive"))
      (node (ref "C56") (pin "2") (pinfunction "2_2") (pintype "passive"))
      (node (ref "C57") (pin "2") (pinfunction "2_2") (pintype "passive"))
      (node (ref "C58") (pin "2") (pinfunction "2_2") (pintype "passive"))
      (node (ref "C59") (pin "2") (pinfunction "2_2") (pintype "passive"))
      (node (ref "C6") (pin "2") (pinfunction "2_2") (pintype "passive"))
      (node (ref "C60") (pin "2") (pinfunction "2_2") (pintype "passive"))
      (node (ref "C61") (pin "2") (pinfunction "2_2") (pintype "passive"))
      (node (ref "C62") (pin "2") (pinfunction "2_2") (pintype "passive"))
      (node (ref "C63") (pin "2") (pinfunction "2_2") (pintype "passive"))
      (node (ref "C64") (pin "2") (pinfunction "2_2") (pintype "passive"))
      (node (ref "C65") (pin "2") (pinfunction "2_2") (pintype "passive"))
      (node (ref "C66") (pin "2") (pinfunction "2_2") (pintype "passive"))
      (node (ref "C7") (pin "2") (pinfunction "2_2") (pintype "passive"))
      (node (ref "C8") (pin "2") (pinfunction "2_2") (pintype "passive"))
      (node (ref "C9") (pin "2") (pinfunction "2_2") (pintype "passive"))
      (node (ref "GREENLED") (pin "C") (pinfunction "C_C") (pintype "passive"))
      (node (ref "JP1") (pin "GND@1") (pinfunction "GND_GND@1") (pintype "bidirectional"))
      (node (ref "JP1") (pin "GND@2") (pinfunction "GND_GND@2") (pintype "bidirectional"))
      (node (ref "JP1") (pin "PGND@1") (pinfunction "PGND_PGND@1") (pintype "bidirectional"))
      (node (ref "JP1") (pin "PGND@2") (pinfunction "PGND_PGND@2") (pintype "bidirectional"))
      (node (ref "JP3") (pin "2") (pinfunction "2_2") (pintype "passive"))
      (node (ref "OV5653_LEFT") (pin "A01") (pinfunction "AGND_A01") (pintype "power_in"))
      (node (ref "OV5653_LEFT") (pin "A02") (pinfunction "TM_A02") (pintype "input"))
      (node (ref "OV5653_LEFT") (pin "A06") (pinfunction "SGND_A06") (pintype "power_in"))
      (node (ref "OV5653_LEFT") (pin "B06") (pinfunction "SGND_B06") (pintype "power_in"))
      (node (ref "OV5653_LEFT") (pin "C09") (pinfunction "AGND_C09") (pintype "power_in"))
      (node (ref "OV5653_LEFT") (pin "C10") (pinfunction "AGND_C10") (pintype "power_in"))
      (node (ref "OV5653_LEFT") (pin "E02") (pinfunction "EGND_E02") (pintype "power_in"))
      (node (ref "OV5653_LEFT") (pin "G09") (pinfunction "AGND_G09") (pintype "power_in"))
      (node (ref "OV5653_LEFT") (pin "G10") (pinfunction "AGND_G10") (pintype "power_in"))
      (node (ref "OV5653_LEFT") (pin "I09") (pinfunction "DGND_I09") (pintype "power_in"))
      (node (ref "OV5653_LEFT") (pin "I10") (pinfunction "DGND_I10") (pintype "power_in"))
      (node (ref "OV5653_LEFT") (pin "J02") (pinfunction "DGND_J02") (pintype "power_in"))
      (node (ref "OV5653_LEFT") (pin "J06") (pinfunction "DOGND_J06") (pintype "power_in"))
      (node (ref "OV5653_RIGHT") (pin "A01") (pinfunction "AGND_A01") (pintype "power_in"))
      (node (ref "OV5653_RIGHT") (pin "A02") (pinfunction "TM_A02") (pintype "input"))
      (node (ref "OV5653_RIGHT") (pin "A06") (pinfunction "SGND_A06") (pintype "power_in"))
      (node (ref "OV5653_RIGHT") (pin "B06") (pinfunction "SGND_B06") (pintype "power_in"))
      (node (ref "OV5653_RIGHT") (pin "C09") (pinfunction "AGND_C09") (pintype "power_in"))
      (node (ref "OV5653_RIGHT") (pin "C10") (pinfunction "AGND_C10") (pintype "power_in"))
      (node (ref "OV5653_RIGHT") (pin "E02") (pinfunction "EGND_E02") (pintype "power_in"))
      (node (ref "OV5653_RIGHT") (pin "G09") (pinfunction "AGND_G09") (pintype "power_in"))
      (node (ref "OV5653_RIGHT") (pin "G10") (pinfunction "AGND_G10") (pintype "power_in"))
      (node (ref "OV5653_RIGHT") (pin "I09") (pinfunction "DGND_I09") (pintype "power_in"))
      (node (ref "OV5653_RIGHT") (pin "I10") (pinfunction "DGND_I10") (pintype "power_in"))
      (node (ref "OV5653_RIGHT") (pin "J02") (pinfunction "DGND_J02") (pintype "power_in"))
      (node (ref "OV5653_RIGHT") (pin "J06") (pinfunction "DOGND_J06") (pintype "power_in"))
      (node (ref "R1") (pin "2") (pinfunction "2_2") (pintype "passive"))
      (node (ref "R2") (pin "2") (pinfunction "2_2") (pintype "passive"))
      (node (ref "R31") (pin "1") (pinfunction "1_1") (pintype "passive"))
      (node (ref "R32") (pin "1") (pinfunction "1_1") (pintype "passive"))
      (node (ref "S1") (pin "1") (pinfunction "1_1") (pintype "passive"))
      (node (ref "U1") (pin "A01") (pinfunction "U3VSSQ_A01") (pintype "bidirectional"))
      (node (ref "U1") (pin "A08") (pinfunction "GND_A08") (pintype "bidirectional"))
      (node (ref "U1") (pin "B02") (pinfunction "FSLC0_B02") (pintype "bidirectional"))
      (node (ref "U1") (pin "B04") (pinfunction "FSLC1_B04") (pintype "bidirectional"))
      (node (ref "U1") (pin "B07") (pinfunction "AGND_B07") (pintype "bidirectional"))
      (node (ref "U1") (pin "B08") (pinfunction "GND_B08") (pintype "bidirectional"))
      (node (ref "U1") (pin "B09") (pinfunction "GND_B09") (pintype "bidirectional"))
      (node (ref "U1") (pin "D08") (pinfunction "GND_D08") (pintype "bidirectional"))
      (node (ref "U1") (pin "E02") (pinfunction "GND_E02") (pintype "bidirectional"))
      (node (ref "U1") (pin "E06") (pinfunction "FSLC2_E06") (pintype "bidirectional"))
      (node (ref "U1") (pin "G01") (pinfunction "GND_G01") (pintype "bidirectional"))
      (node (ref "U1") (pin "G11") (pinfunction "GND_G11") (pintype "bidirectional"))
      (node (ref "U1") (pin "K03") (pinfunction "GND_K03") (pintype "bidirectional"))
      (node (ref "U1") (pin "K04") (pinfunction "GND_K04") (pintype "bidirectional"))
      (node (ref "U1") (pin "L01") (pinfunction "GND_L01") (pintype "bidirectional"))
      (node (ref "U1") (pin "L02") (pinfunction "GND_L02") (pintype "bidirectional"))
      (node (ref "U1") (pin "L03") (pinfunction "GND_L03") (pintype "bidirectional"))
      (node (ref "U1") (pin "L06") (pinfunction "GND_L06") (pintype "bidirectional"))
      (node (ref "U1") (pin "L11") (pinfunction "GND_L11") (pintype "bidirectional"))
      (node (ref "U10") (pin "3") (pinfunction "GND_3") (pintype "power_in"))
      (node (ref "U11") (pin "3") (pinfunction "GND_3") (pintype "power_in"))
      (node (ref "U2") (pin "P3") (pinfunction "3_P3") (pintype "bidirectional"))
      (node (ref "U2") (pin "P8") (pinfunction "8_P8") (pintype "bidirectional"))
      (node (ref "U3") (pin "P2") (pinfunction "GND_P2") (pintype "bidirectional"))
      (node (ref "U4") (pin "4") (pinfunction "VSS_4") (pintype "power_in"))
      (node (ref "U5") (pin "3") (pinfunction "GND_3") (pintype "power_in"))
      (node (ref "U6") (pin "2") (pinfunction "GND_2") (pintype "power_in"))
      (node (ref "U7") (pin "3") (pinfunction "GND_3") (pintype "power_in"))
      (node (ref "U8") (pin "3") (pinfunction "GND_3") (pintype "power_in"))
      (node (ref "U9") (pin "2") (pinfunction "GND_2") (pintype "power_in"))
      (node (ref "Y1") (pin "P2") (pinfunction "P2_P2") (pintype "bidirectional"))
      (node (ref "Y1") (pin "P4") (pinfunction "P4_P4") (pintype "bidirectional"))
    )
    (net (code "21") (name "HREF") (class "Default")
      (node (ref "OV5653_LEFT") (pin "H03") (pinfunction "HREF_H03") (pintype "bidirectional"))
      (node (ref "R24") (pin "1") (pinfunction "1_1") (pintype "passive"))
    )
    (net (code "22") (name "HREF2") (class "Default")
      (node (ref "OV5653_RIGHT") (pin "H03") (pinfunction "HREF_H03") (pintype "bidirectional"))
      (node (ref "R21") (pin "1") (pinfunction "1_1") (pintype "passive"))
    )
    (net (code "23") (name "I2C_SCL") (class "Default")
      (node (ref "OV5653_LEFT") (pin "C03") (pinfunction "SIOC_C03") (pintype "input"))
      (node (ref "OV5653_RIGHT") (pin "C03") (pinfunction "SIOC_C03") (pintype "input"))
      (node (ref "R37") (pin "1") (pinfunction "1_1") (pintype "passive"))
      (node (ref "U1") (pin "D09") (pinfunction "I2C_GPIO58_D09") (pintype "bidirectional"))
      (node (ref "U4") (pin "6") (pinfunction "SCL_6") (pintype "bidirectional"))
    )
    (net (code "24") (name "I2C_SDA") (class "Default")
      (node (ref "OV5653_LEFT") (pin "B01") (pinfunction "SIOD_B01") (pintype "bidirectional"))
      (node (ref "OV5653_RIGHT") (pin "B01") (pinfunction "SIOD_B01") (pintype "bidirectional"))
      (node (ref "R38") (pin "1") (pinfunction "1_1") (pintype "passive"))
      (node (ref "U1") (pin "D10") (pinfunction "I2C_GPIO59_D10") (pintype "bidirectional"))
      (node (ref "U4") (pin "5") (pinfunction "SDA_5") (pintype "bidirectional"))
    )
    (net (code "25") (name "MCLK") (class "Default")
      (node (ref "OV5653_LEFT") (pin "H02") (pinfunction "XVCLK_H02") (pintype "input"))
      (node (ref "OV5653_RIGHT") (pin "H02") (pinfunction "XVCLK_H02") (pintype "input"))
      (node (ref "U9") (pin "3") (pinfunction "OUT_3") (pintype "output"))
    )
    (net (code "26") (name "Net-(F1-1)") (class "Default")
      (node (ref "F1") (pin "P$1") (pinfunction "1_P$1") (pintype "passive"))
      (node (ref "L2") (pin "2") (pinfunction "2_2") (pintype "passive"))
    )
    (net (code "27") (name "Net-(F1-2)") (class "Default")
      (node (ref "C27") (pin "2") (pinfunction "2_2") (pintype "passive"))
      (node (ref "C37") (pin "+") (pinfunction "+_+") (pintype "passive"))
      (node (ref "C39") (pin "1") (pinfunction "1_1") (pintype "passive"))
      (node (ref "F1") (pin "P$2") (pinfunction "2_P$2") (pintype "passive"))
      (node (ref "U1") (pin "E11") (pinfunction "VBUS_E11") (pintype "bidirectional"))
      (node (ref "U3") (pin "P5") (pinfunction "VDD_P5") (pintype "bidirectional"))
      (node (ref "U5") (pin "1") (pinfunction "IN_1") (pintype "power_in"))
      (node (ref "U6") (pin "1") (pinfunction "IN_1") (pintype "power_in"))
      (node (ref "U6") (pin "3") (pinfunction "EN_3") (pintype "input"))
    )
    (net (code "28") (name "Net-(GREENLED-PadA)") (class "Default")
      (node (ref "GREENLED") (pin "A") (pinfunction "A_A") (pintype "passive"))
      (node (ref "R39") (pin "2") (pinfunction "2_2") (pintype "passive"))
    )
    (net (code "29") (name "Net-(JP1-PadVBUS)") (class "Default")
      (node (ref "JP1") (pin "VBUS") (pinfunction "VBUS_VBUS") (pintype "bidirectional"))
      (node (ref "L2") (pin "1") (pinfunction "1_1") (pintype "passive"))
    )
    (net (code "30") (name "Net-(JP2-Pad2)") (class "Default")
      (node (ref "JP2") (pin "2") (pinfunction "2_2") (pintype "passive"))
      (node (ref "R26") (pin "2") (pinfunction "2_2") (pintype "passive"))
    )
    (net (code "31") (name "Net-(JP3-Pad3)") (class "Default")
      (node (ref "JP3") (pin "3") (pinfunction "3_3") (pintype "passive"))
      (node (ref "R27") (pin "1") (pinfunction "1_1") (pintype "passive"))
    )
    (net (code "32") (name "Net-(JP3-Pad4)") (class "Default")
      (node (ref "JP3") (pin "4") (pinfunction "4_4") (pintype "passive"))
      (node (ref "R28") (pin "1") (pinfunction "1_1") (pintype "passive"))
    )
    (net (code "33") (name "Net-(JP3-Pad5)") (class "Default")
      (node (ref "JP3") (pin "5") (pinfunction "5_5") (pintype "passive"))
      (node (ref "R29") (pin "1") (pinfunction "1_1") (pintype "passive"))
    )
    (net (code "34") (name "Net-(JP3-Pad6)") (class "Default")
      (node (ref "JP3") (pin "6") (pinfunction "6_6") (pintype "passive"))
      (node (ref "R30") (pin "1") (pinfunction "1_1") (pintype "passive"))
    )
    (net (code "35") (name "Net-(OV5653_LEFT-FREX)") (class "Default")
      (node (ref "OV5653_LEFT") (pin "B04") (pinfunction "FREX_B04") (pintype "bidirectional"))
      (node (ref "R35") (pin "1") (pinfunction "1_1") (pintype "passive"))
    )
    (net (code "36") (name "Net-(OV5653_LEFT-PWDN)") (class "Default")
      (node (ref "OV5653_LEFT") (pin "B05") (pinfunction "PWDN_B05") (pintype "input"))
      (node (ref "R32") (pin "2") (pinfunction "2_2") (pintype "passive"))
    )
    (net (code "37") (name "Net-(OV5653_LEFT-RESET_B)") (class "Default")
      (node (ref "OV5653_LEFT") (pin "A04") (pinfunction "RESET_B_A04") (pintype "input"))
      (node (ref "R40") (pin "2") (pinfunction "2_2") (pintype "passive"))
      (node (ref "R99") (pin "2") (pinfunction "2_2") (pintype "passive"))
    )
    (net (code "38") (name "Net-(OV5653_LEFT-STROBE)") (class "Default")
      (node (ref "OV5653_LEFT") (pin "A05") (pinfunction "STROBE_A05") (pintype "output"))
      (node (ref "R34") (pin "1") (pinfunction "1_1") (pintype "passive"))
    )
    (net (code "39") (name "Net-(OV5653_LEFT-VH)") (class "Default")
      (node (ref "C46") (pin "1") (pinfunction "1_1") (pintype "passive"))
      (node (ref "OV5653_LEFT") (pin "B08") (pinfunction "VH_B08") (pintype "power_in"))
    )
    (net (code "40") (name "Net-(OV5653_LEFT-VN)") (class "Default")
      (node (ref "C47") (pin "1") (pinfunction "1_1") (pintype "passive"))
      (node (ref "OV5653_LEFT") (pin "A09") (pinfunction "VN_A09") (pintype "power_in"))
    )
    (net (code "41") (name "Net-(OV5653_RIGHT-FREX)") (class "Default")
      (node (ref "OV5653_RIGHT") (pin "B04") (pinfunction "FREX_B04") (pintype "bidirectional"))
      (node (ref "R33") (pin "1") (pinfunction "1_1") (pintype "passive"))
    )
    (net (code "42") (name "Net-(OV5653_RIGHT-PWDN)") (class "Default")
      (node (ref "OV5653_RIGHT") (pin "B05") (pinfunction "PWDN_B05") (pintype "input"))
      (node (ref "R31") (pin "2") (pinfunction "2_2") (pintype "passive"))
    )
    (net (code "43") (name "Net-(OV5653_RIGHT-RESET_B)") (class "Default")
      (node (ref "OV5653_RIGHT") (pin "A04") (pinfunction "RESET_B_A04") (pintype "input"))
      (node (ref "R22") (pin "2") (pinfunction "2_2") (pintype "passive"))
      (node (ref "R98") (pin "2") (pinfunction "2_2") (pintype "passive"))
    )
    (net (code "44") (name "Net-(OV5653_RIGHT-VH)") (class "Default")
      (node (ref "C53") (pin "1") (pinfunction "1_1") (pintype "passive"))
      (node (ref "OV5653_RIGHT") (pin "B08") (pinfunction "VH_B08") (pintype "power_in"))
    )
    (net (code "45") (name "Net-(OV5653_RIGHT-VN)") (class "Default")
      (node (ref "C54") (pin "1") (pinfunction "1_1") (pintype "passive"))
      (node (ref "OV5653_RIGHT") (pin "A09") (pinfunction "VN_A09") (pintype "power_in"))
    )
    (net (code "46") (name "Net-(U1-AVDD)") (class "Default")
      (node (ref "C12") (pin "1") (pinfunction "1_1") (pintype "passive"))
      (node (ref "C13") (pin "1") (pinfunction "1_1") (pintype "passive"))
      (node (ref "L1") (pin "1") (pinfunction "1_1") (pintype "passive"))
      (node (ref "U1") (pin "A07") (pinfunction "AVDD_A07") (pintype "power_in"))
    )
    (net (code "47") (name "Net-(U1-CVDDQ)") (class "Default")
      (node (ref "C25") (pin "1") (pinfunction "1_1") (pintype "passive"))
      (node (ref "C26") (pin "1") (pinfunction "1_1") (pintype "passive"))
      (node (ref "L3") (pin "1") (pinfunction "1_1") (pintype "passive"))
      (node (ref "U1") (pin "B06") (pinfunction "CVDDQ_B06") (pintype "power_in"))
    )
    (net (code "48") (name "Net-(U1-DM)") (class "Default")
      (node (ref "U1") (pin "A10") (pinfunction "DM_A10") (pintype "bidirectional"))
      (node (ref "U3") (pin "P6") (pinfunction "IO1B_P6") (pintype "bidirectional"))
    )
    (net (code "49") (name "Net-(U1-DP)") (class "Default")
      (node (ref "U1") (pin "A09") (pinfunction "DP_A09") (pintype "bidirectional"))
      (node (ref "U3") (pin "P4") (pinfunction "IO2B_P4") (pintype "bidirectional"))
    )
    (net (code "50") (name "Net-(U1-GPIO0)") (class "Default")
      (node (ref "R19") (pin "2") (pinfunction "2_2") (pintype "passive"))
      (node (ref "U1") (pin "F10") (pinfunction "GPIO0_F10") (pintype "bidirectional"))
    )
    (net (code "51") (name "Net-(U1-GPIO1)") (class "Default")
      (node (ref "R18") (pin "2") (pinfunction "2_2") (pintype "passive"))
      (node (ref "U1") (pin "F09") (pinfunction "GPIO1_F09") (pintype "bidirectional"))
    )
    (net (code "52") (name "Net-(U1-GPIO2)") (class "Default")
      (node (ref "R17") (pin "2") (pinfunction "2_2") (pintype "passive"))
      (node (ref "U1") (pin "F07") (pinfunction "GPIO2_F07") (pintype "bidirectional"))
    )
    (net (code "53") (name "Net-(U1-GPIO3)") (class "Default")
      (node (ref "R16") (pin "2") (pinfunction "2_2") (pintype "passive"))
      (node (ref "U1") (pin "G10") (pinfunction "GPIO3_G10") (pintype "bidirectional"))
    )
    (net (code "54") (name "Net-(U1-GPIO4)") (class "Default")
      (node (ref "R15") (pin "2") (pinfunction "2_2") (pintype "passive"))
      (node (ref "U1") (pin "G09") (pinfunction "GPIO4_G09") (pintype "bidirectional"))
    )
    (net (code "55") (name "Net-(U1-GPIO5)") (class "Default")
      (node (ref "R14") (pin "2") (pinfunction "2_2") (pintype "passive"))
      (node (ref "U1") (pin "F08") (pinfunction "GPIO5_F08") (pintype "bidirectional"))
    )
    (net (code "56") (name "Net-(U1-GPIO6)") (class "Default")
      (node (ref "R13") (pin "2") (pinfunction "2_2") (pintype "passive"))
      (node (ref "U1") (pin "H10") (pinfunction "GPIO6_H10") (pintype "bidirectional"))
    )
    (net (code "57") (name "Net-(U1-GPIO7)") (class "Default")
      (node (ref "R12") (pin "2") (pinfunction "2_2") (pintype "passive"))
      (node (ref "U1") (pin "H09") (pinfunction "GPIO7_H09") (pintype "bidirectional"))
    )
    (net (code "58") (name "Net-(U1-GPIO8)") (class "Default")
      (node (ref "R11") (pin "2") (pinfunction "2_2") (pintype "passive"))
      (node (ref "U1") (pin "J10") (pinfunction "GPIO8_J10") (pintype "bidirectional"))
    )
    (net (code "59") (name "Net-(U1-GPIO9)") (class "Default")
      (node (ref "R10") (pin "2") (pinfunction "2_2") (pintype "passive"))
      (node (ref "U1") (pin "J09") (pinfunction "GPIO9_J09") (pintype "bidirectional"))
    )
    (net (code "60") (name "Net-(U1-GPIO10)") (class "Default")
      (node (ref "R9") (pin "2") (pinfunction "2_2") (pintype "passive"))
      (node (ref "U1") (pin "K11") (pinfunction "GPIO10_K11") (pintype "bidirectional"))
    )
    (net (code "61") (name "Net-(U1-GPIO11)") (class "Default")
      (node (ref "R8") (pin "2") (pinfunction "2_2") (pintype "passive"))
      (node (ref "U1") (pin "L10") (pinfunction "GPIO11_L10") (pintype "bidirectional"))
    )
    (net (code "62") (name "Net-(U1-GPIO12)") (class "Default")
      (node (ref "R7") (pin "2") (pinfunction "2_2") (pintype "passive"))
      (node (ref "U1") (pin "K10") (pinfunction "GPIO12_K10") (pintype "bidirectional"))
    )
    (net (code "63") (name "Net-(U1-GPIO13)") (class "Default")
      (node (ref "R6") (pin "2") (pinfunction "2_2") (pintype "passive"))
      (node (ref "U1") (pin "K09") (pinfunction "GPIO13_K09") (pintype "bidirectional"))
    )
    (net (code "64") (name "Net-(U1-GPIO14)") (class "Default")
      (node (ref "R5") (pin "2") (pinfunction "2_2") (pintype "passive"))
      (node (ref "U1") (pin "J08") (pinfunction "GPIO14_J08") (pintype "bidirectional"))
    )
    (net (code "65") (name "Net-(U1-GPIO15)") (class "Default")
      (node (ref "R4") (pin "2") (pinfunction "2_2") (pintype "passive"))
      (node (ref "U1") (pin "G08") (pinfunction "GPIO15_G08") (pintype "bidirectional"))
    )
    (net (code "66") (name "Net-(U1-GPIO16)") (class "Default")
      (node (ref "R3") (pin "2") (pinfunction "2_2") (pintype "passive"))
      (node (ref "U1") (pin "J06") (pinfunction "GPIO16_J06") (pintype "bidirectional"))
    )
    (net (code "67") (name "Net-(U1-GPIO26)") (class "Default")
      (node (ref "R24") (pin "2") (pinfunction "2_2") (pintype "passive"))
      (node (ref "U1") (pin "H06") (pinfunction "GPIO26_H06") (pintype "bidirectional"))
    )
    (net (code "68") (name "Net-(U1-GPIO27)") (class "Default")
      (node (ref "R23") (pin "2") (pinfunction "2_2") (pintype "passive"))
      (node (ref "U1") (pin "K05") (pinfunction "GPIO27_K05") (pintype "bidirectional"))
    )
    (net (code "69") (name "Net-(U1-GPIO28)") (class "Default")
      (node (ref "R21") (pin "2") (pinfunction "2_2") (pintype "passive"))
      (node (ref "U1") (pin "J05") (pinfunction "GPIO28_J05") (pintype "bidirectional"))
    )
    (net (code "70") (name "Net-(U1-GPIO29)") (class "Default")
      (node (ref "R20") (pin "2") (pinfunction "2_2") (pintype "passive"))
      (node (ref "U1") (pin "H05") (pinfunction "GPIO29_H05") (pintype "bidirectional"))
    )
    (net (code "71") (name "Net-(U1-GPIO30{slash}PMODE0)") (class "Default")
      (node (ref "JP2") (pin "1") (pinfunction "1_1") (pintype "passive"))
      (node (ref "U1") (pin "G04") (pinfunction "GPIO30/PMODE0_G04") (pintype "bidirectional"))
    )
    (net (code "72") (name "Net-(U1-GPIO31{slash}PMODE1)") (class "Default")
      (node (ref "R25") (pin "2") (pinfunction "2_2") (pintype "passive"))
      (node (ref "U1") (pin "H04") (pinfunction "GPIO31/PMODE1_H04") (pintype "bidirectional"))
    )
    (net (code "73") (name "Net-(U1-GPIO35)") (class "Default")
      (node (ref "R30") (pin "2") (pinfunction "2_2") (pintype "passive"))
      (node (ref "U1") (pin "K01") (pinfunction "GPIO35_K01") (pintype "bidirectional"))
    )
    (net (code "74") (name "Net-(U1-GPIO36)") (class "Default")
      (node (ref "R29") (pin "2") (pinfunction "2_2") (pintype "passive"))
      (node (ref "U1") (pin "J02") (pinfunction "GPIO36_J02") (pintype "bidirectional"))
    )
    (net (code "75") (name "Net-(U1-GPIO37)") (class "Default")
      (node (ref "R28") (pin "2") (pinfunction "2_2") (pintype "passive"))
      (node (ref "U1") (pin "J03") (pinfunction "GPIO37_J03") (pintype "bidirectional"))
    )
    (net (code "76") (name "Net-(U1-GPIO38)") (class "Default")
      (node (ref "R27") (pin "2") (pinfunction "2_2") (pintype "passive"))
      (node (ref "U1") (pin "J01") (pinfunction "GPIO38_J01") (pintype "bidirectional"))
    )
    (net (code "77") (name "Net-(U1-R_USB2)") (class "Default")
      (node (ref "R1") (pin "1") (pinfunction "1_1") (pintype "passive"))
      (node (ref "U1") (pin "C08") (pinfunction "R_USB2_C08") (pintype "bidirectional"))
    )
    (net (code "78") (name "Net-(U1-R_USB3)") (class "Default")
      (node (ref "R2") (pin "1") (pinfunction "1_1") (pintype "passive"))
      (node (ref "U1") (pin "B03") (pinfunction "R_USB3_B03") (pintype "bidirectional"))
    )
    (net (code "79") (name "Net-(U1-SSTXM)") (class "Default")
      (node (ref "C28") (pin "2") (pinfunction "2_2") (pintype "passive"))
      (node (ref "U1") (pin "A06") (pinfunction "SSTXM_A06") (pintype "bidirectional"))
    )
    (net (code "80") (name "Net-(U1-SSTXP)") (class "Default")
      (node (ref "C29") (pin "2") (pinfunction "2_2") (pintype "passive"))
      (node (ref "U1") (pin "A05") (pinfunction "SSTXP_A05") (pintype "bidirectional"))
    )
    (net (code "81") (name "Net-(U1-U3RXVDDQ)") (class "Default")
      (node (ref "C32") (pin "1") (pinfunction "1_1") (pintype "passive"))
      (node (ref "C33") (pin "1") (pinfunction "1_1") (pintype "passive"))
      (node (ref "L5") (pin "1") (pinfunction "1_1") (pintype "passive"))
      (node (ref "U1") (pin "A02") (pinfunction "U3RXVDDQ_A02") (pintype "power_in"))
    )
    (net (code "82") (name "Net-(U1-U3TXVDDQ)") (class "Default")
      (node (ref "C30") (pin "1") (pinfunction "1_1") (pintype "passive"))
      (node (ref "C31") (pin "1") (pinfunction "1_1") (pintype "passive"))
      (node (ref "L4") (pin "1") (pinfunction "1_1") (pintype "passive"))
      (node (ref "U1") (pin "B05") (pinfunction "U3TXVDDQ_B05") (pintype "power_in"))
    )
    (net (code "83") (name "Net-(U1-XTALIN)") (class "Default")
      (node (ref "C34") (pin "1") (pinfunction "1_1") (pintype "passive"))
      (node (ref "U1") (pin "C06") (pinfunction "XTALIN_C06") (pintype "bidirectional"))
      (node (ref "Y1") (pin "P1") (pinfunction "P1_P1") (pintype "bidirectional"))
    )
    (net (code "84") (name "Net-(U1-XTALOUT)") (class "Default")
      (node (ref "C35") (pin "1") (pinfunction "1_1") (pintype "passive"))
      (node (ref "U1") (pin "C07") (pinfunction "XTALOUT_C07") (pintype "bidirectional"))
      (node (ref "Y1") (pin "P3") (pinfunction "P3_P3") (pintype "bidirectional"))
    )
    (net (code "85") (name "Net-(U3-IO2A)") (class "Default")
      (node (ref "JP1") (pin "USB2_DP") (pinfunction "USB2_DP_USB2_DP") (pintype "bidirectional"))
      (node (ref "U3") (pin "P3") (pinfunction "IO2A_P3") (pintype "bidirectional"))
    )
    (net (code "86") (name "Net-(U3-IOA1)") (class "Default")
      (node (ref "JP1") (pin "USB2_DM") (pinfunction "USB2_DM_USB2_DM") (pintype "bidirectional"))
      (node (ref "U3") (pin "P1") (pinfunction "IOA1_P1") (pintype "bidirectional"))
    )
    (net (code "87") (name "Net-(U6-SW)") (class "Default")
      (node (ref "L6") (pin "1") (pinfunction "1_1") (pintype "passive"))
      (node (ref "U6") (pin "5") (pinfunction "SW_5") (pintype "bidirectional"))
    )
    (net (code "88") (name "Net-(U7-OUT)") (class "Default")
      (node (ref "C44") (pin "1") (pinfunction "1_1") (pintype "passive"))
      (node (ref "L7") (pin "1") (pinfunction "1_1") (pintype "passive"))
      (node (ref "U7") (pin "2") (pinfunction "OUT_2") (pintype "power_in"))
    )
    (net (code "89") (name "Net-(U8-OUT)") (class "Default")
      (node (ref "C43") (pin "1") (pinfunction "1_1") (pintype "passive"))
      (node (ref "L8") (pin "1") (pinfunction "1_1") (pintype "passive"))
      (node (ref "U8") (pin "2") (pinfunction "OUT_2") (pintype "power_in"))
    )
    (net (code "90") (name "Net-(U10-OUT)") (class "Default")
      (node (ref "C60") (pin "1") (pinfunction "1_1") (pintype "passive"))
      (node (ref "L9") (pin "1") (pinfunction "1_1") (pintype "passive"))
      (node (ref "U10") (pin "2") (pinfunction "OUT_2") (pintype "power_in"))
    )
    (net (code "91") (name "Net-(U11-OUT)") (class "Default")
      (node (ref "C63") (pin "1") (pinfunction "1_1") (pintype "passive"))
      (node (ref "L10") (pin "1") (pinfunction "1_1") (pintype "passive"))
      (node (ref "U11") (pin "2") (pinfunction "OUT_2") (pintype "power_in"))
    )
    (net (code "92") (name "PCLK") (class "Default")
      (node (ref "OV5653_LEFT") (pin "J03") (pinfunction "PCLK_J03") (pintype "output"))
      (node (ref "R3") (pin "1") (pinfunction "1_1") (pintype "passive"))
    )
    (net (code "93") (name "PCLK2") (class "Default")
      (node (ref "OV5653_RIGHT") (pin "J03") (pinfunction "PCLK_J03") (pintype "output"))
    )
    (net (code "94") (name "RESET_IN") (class "Default")
      (node (ref "C41") (pin "1") (pinfunction "1_1") (pintype "passive"))
      (node (ref "R36") (pin "2") (pinfunction "2_2") (pintype "passive"))
      (node (ref "S1") (pin "2") (pinfunction "2_2") (pintype "passive"))
      (node (ref "U1") (pin "C05") (pinfunction "RESET#_C05") (pintype "bidirectional"))
    )
    (net (code "95") (name "SS_RX_M") (class "Default")
      (node (ref "JP1") (pin "USB3_RXDM") (pinfunction "USB3_RXDM_USB3_RXDM") (pintype "bidirectional"))
      (node (ref "U1") (pin "A04") (pinfunction "SSRXP_A04") (pintype "bidirectional"))
      (node (ref "U2") (pin "P4") (pinfunction "4_P4") (pintype "bidirectional"))
      (node (ref "U2") (pin "P7") (pinfunction "7_P7") (pintype "bidirectional"))
    )
    (net (code "96") (name "SS_RX_P") (class "Default")
      (node (ref "JP1") (pin "USB3_RXDP") (pinfunction "USB3_RXDP_USB3_RXDP") (pintype "bidirectional"))
      (node (ref "U1") (pin "A03") (pinfunction "SSRXM_A03") (pintype "bidirectional"))
      (node (ref "U2") (pin "P5") (pinfunction "5_P5") (pintype "bidirectional"))
      (node (ref "U2") (pin "P6") (pinfunction "6_P6") (pintype "bidirectional"))
    )
    (net (code "97") (name "SS_TX_M") (class "Default")
      (node (ref "C28") (pin "1") (pinfunction "1_1") (pintype "passive"))
      (node (ref "JP1") (pin "USB3_TXDM") (pinfunction "USB3_TXDM_USB3_TXDM") (pintype "bidirectional"))
      (node (ref "U2") (pin "P1") (pinfunction "1_P1") (pintype "bidirectional"))
      (node (ref "U2") (pin "P10") (pinfunction "10_P10") (pintype "bidirectional"))
    )
    (net (code "98") (name "SS_TX_P") (class "Default")
      (node (ref "C29") (pin "1") (pinfunction "1_1") (pintype "passive"))
      (node (ref "JP1") (pin "USB3_TXDP") (pinfunction "USB3_TXDP_USB3_TXDP") (pintype "bidirectional"))
      (node (ref "U2") (pin "P2") (pinfunction "2_P2") (pintype "bidirectional"))
      (node (ref "U2") (pin "P9") (pinfunction "9_P9") (pintype "bidirectional"))
    )
    (net (code "99") (name "STROBE") (class "Default")
      (node (ref "R34") (pin "2") (pinfunction "2_2") (pintype "passive"))
      (node (ref "U1") (pin "D04") (pinfunction "GPIO53_D04") (pintype "bidirectional"))
    )
    (net (code "100") (name "VCC") (class "Default")
      (node (ref "C49") (pin "1") (pinfunction "1_1") (pintype "passive"))
      (node (ref "L8") (pin "2") (pinfunction "2_2") (pintype "passive"))
      (node (ref "OV5653_LEFT") (pin "F01") (pinfunction "EVDD_F01") (pintype "power_in"))
      (node (ref "OV5653_LEFT") (pin "J01") (pinfunction "DVDD_J01") (pintype "power_in"))
      (node (ref "OV5653_LEFT") (pin "J07") (pinfunction "DVDD_J07") (pintype "power_in"))
    )
    (net (code "101") (name "VCC2") (class "Default")
      (node (ref "C56") (pin "1") (pinfunction "1_1") (pintype "passive"))
      (node (ref "L10") (pin "2") (pinfunction "2_2") (pintype "passive"))
      (node (ref "OV5653_RIGHT") (pin "F01") (pinfunction "EVDD_F01") (pintype "power_in"))
      (node (ref "OV5653_RIGHT") (pin "J01") (pinfunction "DVDD_J01") (pintype "power_in"))
      (node (ref "OV5653_RIGHT") (pin "J07") (pinfunction "DVDD_J07") (pintype "power_in"))
    )
    (net (code "102") (name "VCCIO") (class "Default")
      (node (ref "C14") (pin "1") (pinfunction "1_1") (pintype "passive"))
      (node (ref "C15") (pin "1") (pinfunction "1_1") (pintype "passive"))
      (node (ref "C16") (pin "1") (pinfunction "1_1") (pintype "passive"))
      (node (ref "C17") (pin "1") (pinfunction "1_1") (pintype "passive"))
      (node (ref "C18") (pin "1") (pinfunction "1_1") (pintype "passive"))
      (node (ref "C19") (pin "1") (pinfunction "1_1") (pintype "passive"))
      (node (ref "C22") (pin "1") (pinfunction "1_1") (pintype "passive"))
      (node (ref "C23") (pin "1") (pinfunction "1_1") (pintype "passive"))
      (node (ref "C24") (pin "1") (pinfunction "1_1") (pintype "passive"))
      (node (ref "C36") (pin "1") (pinfunction "1_1") (pintype "passive"))
      (node (ref "C48") (pin "1") (pinfunction "1_1") (pintype "passive"))
      (node (ref "C50") (pin "1") (pinfunction "1_1") (pintype "passive"))
      (node (ref "C51") (pin "1") (pinfunction "1_1") (pintype "passive"))
      (node (ref "C52") (pin "1") (pinfunction "1_1") (pintype "passive"))
      (node (ref "C55") (pin "1") (pinfunction "1_1") (pintype "passive"))
      (node (ref "C57") (pin "1") (pinfunction "1_1") (pintype "passive"))
      (node (ref "C58") (pin "1") (pinfunction "1_1") (pintype "passive"))
      (node (ref "C59") (pin "1") (pinfunction "1_1") (pintype "passive"))
      (node (ref "C64") (pin "1") (pinfunction "1_1") (pintype "passive"))
      (node (ref "C65") (pin "1") (pinfunction "1_1") (pintype "passive"))
      (node (ref "C66") (pin "1") (pinfunction "1_1") (pintype "passive"))
      (node (ref "JP3") (pin "1") (pinfunction "1_1") (pintype "passive"))
      (node (ref "L7") (pin "2") (pinfunction "2_2") (pintype "passive"))
      (node (ref "L9") (pin "2") (pinfunction "2_2") (pintype "passive"))
      (node (ref "OV5653_LEFT") (pin "A03") (pinfunction "DOVDD_A03") (pintype "power_in"))
      (node (ref "OV5653_LEFT") (pin "A07") (pinfunction "SVDD_A07") (pintype "power_in"))
      (node (ref "OV5653_LEFT") (pin "A08") (pinfunction "VHT_A08") (pintype "power_in"))
      (node (ref "OV5653_LEFT") (pin "B02") (pinfunction "AVDD_B02") (pintype "power_in"))
      (node (ref "OV5653_LEFT") (pin "B07") (pinfunction "SVDD_B07") (pintype "power_in"))
      (node (ref "OV5653_LEFT") (pin "B09") (pinfunction "AVDD_B09") (pintype "power_in"))
      (node (ref "OV5653_LEFT") (pin "B10") (pinfunction "AVDD_B10") (pintype "power_in"))
      (node (ref "OV5653_LEFT") (pin "H01") (pinfunction "PVDD_H01") (pintype "power_in"))
      (node (ref "OV5653_LEFT") (pin "H09") (pinfunction "AVDD_H09") (pintype "power_in"))
      (node (ref "OV5653_LEFT") (pin "H10") (pinfunction "AVDD_H10") (pintype "power_in"))
      (node (ref "OV5653_LEFT") (pin "I01") (pinfunction "DOVDD_I01") (pintype "power_in"))
      (node (ref "OV5653_LEFT") (pin "I02") (pinfunction "DOVDD_I02") (pintype "power_in"))
      (node (ref "OV5653_LEFT") (pin "I06") (pinfunction "DOVDD_I06") (pintype "power_in"))
      (node (ref "OV5653_RIGHT") (pin "A03") (pinfunction "DOVDD_A03") (pintype "power_in"))
      (node (ref "OV5653_RIGHT") (pin "A07") (pinfunction "SVDD_A07") (pintype "power_in"))
      (node (ref "OV5653_RIGHT") (pin "A08") (pinfunction "VHT_A08") (pintype "power_in"))
      (node (ref "OV5653_RIGHT") (pin "B02") (pinfunction "AVDD_B02") (pintype "power_in"))
      (node (ref "OV5653_RIGHT") (pin "B07") (pinfunction "SVDD_B07") (pintype "power_in"))
      (node (ref "OV5653_RIGHT") (pin "B09") (pinfunction "AVDD_B09") (pintype "power_in"))
      (node (ref "OV5653_RIGHT") (pin "B10") (pinfunction "AVDD_B10") (pintype "power_in"))
      (node (ref "OV5653_RIGHT") (pin "H01") (pinfunction "PVDD_H01") (pintype "power_in"))
      (node (ref "OV5653_RIGHT") (pin "H09") (pinfunction "AVDD_H09") (pintype "power_in"))
      (node (ref "OV5653_RIGHT") (pin "H10") (pinfunction "AVDD_H10") (pintype "power_in"))
      (node (ref "OV5653_RIGHT") (pin "I01") (pinfunction "DOVDD_I01") (pintype "power_in"))
      (node (ref "OV5653_RIGHT") (pin "I02") (pinfunction "DOVDD_I02") (pintype "power_in"))
      (node (ref "OV5653_RIGHT") (pin "I06") (pinfunction "DOVDD_I06") (pintype "power_in"))
      (node (ref "R22") (pin "1") (pinfunction "1_1") (pintype "passive"))
      (node (ref "R25") (pin "1") (pinfunction "1_1") (pintype "passive"))
      (node (ref "R26") (pin "1") (pinfunction "1_1") (pintype "passive"))
      (node (ref "R37") (pin "2") (pinfunction "2_2") (pintype "passive"))
      (node (ref "R38") (pin "2") (pinfunction "2_2") (pintype "passive"))
      (node (ref "R40") (pin "1") (pinfunction "1_1") (pintype "passive"))
      (node (ref "U1") (pin "C11") (pinfunction "VIO5_C11") (pintype "power_in"))
      (node (ref "U1") (pin "E03") (pinfunction "VIO3_E03") (pintype "power_in"))
      (node (ref "U1") (pin "F01") (pinfunction "VIO2_F01") (pintype "power_in"))
      (node (ref "U1") (pin "H11") (pinfunction "VIO1_H11") (pintype "power_in"))
      (node (ref "U1") (pin "L09") (pinfunction "VIO1_L09") (pintype "power_in"))
      (node (ref "U4") (pin "8") (pinfunction "VCC_8") (pintype "power_in"))
      (node (ref "U9") (pin "4") (pinfunction "VCC_4") (pintype "power_in"))
    )
    (net (code "103") (name "VSYNC") (class "Default")
      (node (ref "OV5653_LEFT") (pin "B03") (pinfunction "VSYNC_B03") (pintype "bidirectional"))
      (node (ref "R23") (pin "1") (pinfunction "1_1") (pintype "passive"))
    )
    (net (code "104") (name "VSYNC2") (class "Default")
      (node (ref "OV5653_RIGHT") (pin "B03") (pinfunction "VSYNC_B03") (pintype "bidirectional"))
      (node (ref "R20") (pin "1") (pinfunction "1_1") (pintype "passive"))
    )
    (net (code "105") (name "unconnected-(JP1-OTG-PadUSBOTG)") (class "Default")
      (node (ref "JP1") (pin "USBOTG") (pinfunction "OTG_USBOTG") (pintype "bidirectional"))
    )
    (net (code "106") (name "unconnected-(OV5653_LEFT-D0-PadI03)") (class "Default")
      (node (ref "OV5653_LEFT") (pin "I03") (pinfunction "D0_I03") (pintype "bidirectional"))
    )
    (net (code "107") (name "unconnected-(OV5653_LEFT-D1-PadJ04)") (class "Default")
      (node (ref "OV5653_LEFT") (pin "J04") (pinfunction "D1_J04") (pintype "bidirectional"))
    )
    (net (code "108") (name "unconnected-(OV5653_LEFT-MCN-PadE01)") (class "Default")
      (node (ref "OV5653_LEFT") (pin "E01") (pinfunction "MCN_E01") (pintype "output"))
    )
    (net (code "109") (name "unconnected-(OV5653_LEFT-MCP-PadD01)") (class "Default")
      (node (ref "OV5653_LEFT") (pin "D01") (pinfunction "MCP_D01") (pintype "output"))
    )
    (net (code "110") (name "unconnected-(OV5653_LEFT-MDN1-PadG02)") (class "Default")
      (node (ref "OV5653_LEFT") (pin "G02") (pinfunction "MDN1_G02") (pintype "output"))
    )
    (net (code "111") (name "unconnected-(OV5653_LEFT-MDN2-PadD02)") (class "Default")
      (node (ref "OV5653_LEFT") (pin "D02") (pinfunction "MDN2_D02") (pintype "output"))
    )
    (net (code "112") (name "unconnected-(OV5653_LEFT-MDP1-PadF02)") (class "Default")
      (node (ref "OV5653_LEFT") (pin "F02") (pinfunction "MDP1_F02") (pintype "output"))
    )
    (net (code "113") (name "unconnected-(OV5653_LEFT-MDP2-PadC02)") (class "Default")
      (node (ref "OV5653_LEFT") (pin "C02") (pinfunction "MDP2_C02") (pintype "output"))
    )
    (net (code "114") (name "unconnected-(OV5653_RIGHT-D0-PadI03)") (class "Default")
      (node (ref "OV5653_RIGHT") (pin "I03") (pinfunction "D0_I03") (pintype "bidirectional"))
    )
    (net (code "115") (name "unconnected-(OV5653_RIGHT-D1-PadJ04)") (class "Default")
      (node (ref "OV5653_RIGHT") (pin "J04") (pinfunction "D1_J04") (pintype "bidirectional"))
    )
    (net (code "116") (name "unconnected-(OV5653_RIGHT-MCN-PadE01)") (class "Default")
      (node (ref "OV5653_RIGHT") (pin "E01") (pinfunction "MCN_E01") (pintype "output"))
    )
    (net (code "117") (name "unconnected-(OV5653_RIGHT-MCP-PadD01)") (class "Default")
      (node (ref "OV5653_RIGHT") (pin "D01") (pinfunction "MCP_D01") (pintype "output"))
    )
    (net (code "118") (name "unconnected-(OV5653_RIGHT-MDN1-PadG02)") (class "Default")
      (node (ref "OV5653_RIGHT") (pin "G02") (pinfunction "MDN1_G02") (pintype "output"))
    )
    (net (code "119") (name "unconnected-(OV5653_RIGHT-MDN2-PadD02)") (class "Default")
      (node (ref "OV5653_RIGHT") (pin "D02") (pinfunction "MDN2_D02") (pintype "output"))
    )
    (net (code "120") (name "unconnected-(OV5653_RIGHT-MDP1-PadF02)") (class "Default")
      (node (ref "OV5653_RIGHT") (pin "F02") (pinfunction "MDP1_F02") (pintype "output"))
    )
    (net (code "121") (name "unconnected-(OV5653_RIGHT-MDP2-PadC02)") (class "Default")
      (node (ref "OV5653_RIGHT") (pin "C02") (pinfunction "MDP2_C02") (pintype "output"))
    )
    (net (code "122") (name "unconnected-(OV5653_RIGHT-STROBE-PadA05)") (class "Default")
      (node (ref "OV5653_RIGHT") (pin "A05") (pinfunction "STROBE_A05") (pintype "output"))
    )
    (net (code "123") (name "unconnected-(U1-CLKIN-PadD07)") (class "Default")
      (node (ref "U1") (pin "D07") (pinfunction "CLKIN_D07") (pintype "bidirectional"))
    )
    (net (code "124") (name "unconnected-(U1-CLKIN_32-PadD06)") (class "Default")
      (node (ref "U1") (pin "D06") (pinfunction "CLKIN_32_D06") (pintype "bidirectional"))
    )
    (net (code "125") (name "unconnected-(U1-GPIO17-PadK08)") (class "Default")
      (node (ref "U1") (pin "K08") (pinfunction "GPIO17_K08") (pintype "bidirectional"))
    )
    (net (code "126") (name "unconnected-(U1-GPIO18-PadK07)") (class "Default")
      (node (ref "U1") (pin "K07") (pinfunction "GPIO18_K07") (pintype "bidirectional"))
    )
    (net (code "127") (name "unconnected-(U1-GPIO19-PadJ07)") (class "Default")
      (node (ref "U1") (pin "J07") (pinfunction "GPIO19_J07") (pintype "bidirectional"))
    )
    (net (code "128") (name "unconnected-(U1-GPIO20-PadH07)") (class "Default")
      (node (ref "U1") (pin "H07") (pinfunction "GPIO20_H07") (pintype "bidirectional"))
    )
    (net (code "129") (name "unconnected-(U1-GPIO21-PadG07)") (class "Default")
      (node (ref "U1") (pin "G07") (pinfunction "GPIO21_G07") (pintype "bidirectional"))
    )
    (net (code "130") (name "unconnected-(U1-GPIO22-PadG06)") (class "Default")
      (node (ref "U1") (pin "G06") (pinfunction "GPIO22_G06") (pintype "bidirectional"))
    )
    (net (code "131") (name "unconnected-(U1-GPIO23-PadK06)") (class "Default")
      (node (ref "U1") (pin "K06") (pinfunction "GPIO23_K06") (pintype "bidirectional"))
    )
    (net (code "132") (name "unconnected-(U1-GPIO24-PadH08)") (class "Default")
      (node (ref "U1") (pin "H08") (pinfunction "GPIO24_H08") (pintype "bidirectional"))
    )
    (net (code "133") (name "unconnected-(U1-GPIO32{slash}PMODE2-PadL04)") (class "Default")
      (node (ref "U1") (pin "L04") (pinfunction "GPIO32/PMODE2_L04") (pintype "bidirectional"))
    )
    (net (code "134") (name "unconnected-(U1-GPIO33-PadK02)") (class "Default")
      (node (ref "U1") (pin "K02") (pinfunction "GPIO33_K02") (pintype "bidirectional"))
    )
    (net (code "135") (name "unconnected-(U1-GPIO34-PadJ04)") (class "Default")
      (node (ref "U1") (pin "J04") (pinfunction "GPIO34_J04") (pintype "bidirectional"))
    )
    (net (code "136") (name "unconnected-(U1-GPIO39-PadH02)") (class "Default")
      (node (ref "U1") (pin "H02") (pinfunction "GPIO39_H02") (pintype "bidirectional"))
    )
    (net (code "137") (name "unconnected-(U1-GPIO40-PadH03)") (class "Default")
      (node (ref "U1") (pin "H03") (pinfunction "GPIO40_H03") (pintype "bidirectional"))
    )
    (net (code "138") (name "unconnected-(U1-GPIO41-PadF04)") (class "Default")
      (node (ref "U1") (pin "F04") (pinfunction "GPIO41_F04") (pintype "bidirectional"))
    )
    (net (code "139") (name "unconnected-(U1-GPIO42-PadG02)") (class "Default")
      (node (ref "U1") (pin "G02") (pinfunction "GPIO42_G02") (pintype "bidirectional"))
    )
    (net (code "140") (name "unconnected-(U1-GPIO43-PadG03)") (class "Default")
      (node (ref "U1") (pin "G03") (pinfunction "GPIO43_G03") (pintype "bidirectional"))
    )
    (net (code "141") (name "unconnected-(U1-GPIO44-PadF03)") (class "Default")
      (node (ref "U1") (pin "F03") (pinfunction "GPIO44_F03") (pintype "bidirectional"))
    )
    (net (code "142") (name "unconnected-(U1-GPIO45-PadF02)") (class "Default")
      (node (ref "U1") (pin "F02") (pinfunction "GPIO45_F02") (pintype "bidirectional"))
    )
    (net (code "143") (name "unconnected-(U1-GPIO46-PadF05)") (class "Default")
      (node (ref "U1") (pin "F05") (pinfunction "GPIO46_F05") (pintype "bidirectional"))
    )
    (net (code "144") (name "unconnected-(U1-GPIO47-PadE01)") (class "Default")
      (node (ref "U1") (pin "E01") (pinfunction "GPIO47_E01") (pintype "bidirectional"))
    )
    (net (code "145") (name "unconnected-(U1-GPIO48-PadE05)") (class "Default")
      (node (ref "U1") (pin "E05") (pinfunction "GPIO48_E05") (pintype "bidirectional"))
    )
    (net (code "146") (name "unconnected-(U1-GPIO49-PadE04)") (class "Default")
      (node (ref "U1") (pin "E04") (pinfunction "GPIO49_E04") (pintype "bidirectional"))
    )
    (net (code "147") (name "unconnected-(U1-GPIO50-PadD01)") (class "Default")
      (node (ref "U1") (pin "D01") (pinfunction "GPIO50_D01") (pintype "bidirectional"))
    )
    (net (code "148") (name "unconnected-(U1-GPIO51-PadD02)") (class "Default")
      (node (ref "U1") (pin "D02") (pinfunction "GPIO51_D02") (pintype "bidirectional"))
    )
    (net (code "149") (name "unconnected-(U1-GPIO52-PadD03)") (class "Default")
      (node (ref "U1") (pin "D03") (pinfunction "GPIO52_D03") (pintype "bidirectional"))
    )
    (net (code "150") (name "unconnected-(U1-GPIO54-PadC01)") (class "Default")
      (node (ref "U1") (pin "C01") (pinfunction "GPIO54_C01") (pintype "bidirectional"))
    )
    (net (code "151") (name "unconnected-(U1-GPIO55-PadC02)") (class "Default")
      (node (ref "U1") (pin "C02") (pinfunction "GPIO55_C02") (pintype "bidirectional"))
    )
    (net (code "152") (name "unconnected-(U1-GPIO56-PadD05)") (class "Default")
      (node (ref "U1") (pin "D05") (pinfunction "GPIO56_D05") (pintype "bidirectional"))
    )
    (net (code "153") (name "unconnected-(U1-GPIO57-PadC04)") (class "Default")
      (node (ref "U1") (pin "C04") (pinfunction "GPIO57_C04") (pintype "bidirectional"))
    )
    (net (code "154") (name "unconnected-(U1-INT#-PadL08)") (class "Default")
      (node (ref "U1") (pin "L08") (pinfunction "INT#_L08") (pintype "bidirectional"))
    )
    (net (code "155") (name "unconnected-(U1-JTAG_TCK-PadF06)") (class "Default")
      (node (ref "U1") (pin "F06") (pinfunction "JTAG_TCK_F06") (pintype "bidirectional"))
    )
    (net (code "156") (name "unconnected-(U1-JTAG_TDI-PadE07)") (class "Default")
      (node (ref "U1") (pin "E07") (pinfunction "JTAG_TDI_E07") (pintype "bidirectional"))
    )
    (net (code "157") (name "unconnected-(U1-JTAG_TDO-PadC10)") (class "Default")
      (node (ref "U1") (pin "C10") (pinfunction "JTAG_TDO_C10") (pintype "bidirectional"))
    )
    (net (code "158") (name "unconnected-(U1-JTAG_TMS-PadE08)") (class "Default")
      (node (ref "U1") (pin "E08") (pinfunction "JTAG_TMS_E08") (pintype "bidirectional"))
    )
    (net (code "159") (name "unconnected-(U1-O60-PadD11)") (class "Default")
      (node (ref "U1") (pin "D11") (pinfunction "O60_D11") (pintype "bidirectional"))
    )
    (net (code "160") (name "unconnected-(U1-OTG_ID-PadC09)") (class "Default")
      (node (ref "U1") (pin "C09") (pinfunction "OTG_ID_C09") (pintype "bidirectional"))
    )
    (net (code "161") (name "unconnected-(U1-TRST#-PadB11)") (class "Default")
      (node (ref "U1") (pin "B11") (pinfunction "TRST#_B11") (pintype "bidirectional"))
    )
    (net (code "162") (name "unconnected-(U1-VBATT-PadE10)") (class "Default")
      (node (ref "U1") (pin "E10") (pinfunction "VBATT_E10") (pintype "bidirectional"))
    )
    (net (code "163") (name "unconnected-(U4-DU1-Pad1)") (class "Default")
      (node (ref "U4") (pin "1") (pinfunction "DU1_1") (pintype "bidirectional"))
    )
    (net (code "164") (name "unconnected-(U4-DU2-Pad2)") (class "Default")
      (node (ref "U4") (pin "2") (pinfunction "DU2_2") (pintype "bidirectional"))
    )
    (net (code "165") (name "unconnected-(U4-E2-Pad3)") (class "Default")
      (node (ref "U4") (pin "3") (pinfunction "E2_3") (pintype "bidirectional"))
    )
    (net (code "166") (name "unconnected-(U4-~{WC}-Pad7)") (class "Default")
      (node (ref "U4") (pin "7") (pinfunction "~{WC}_7") (pintype "bidirectional"))
    )
    (net (code "167") (name "unconnected-(U9-~{INH}-Pad1)") (class "Default")
      (node (ref "U9") (pin "1") (pinfunction "~{INH}_1") (pintype "bidirectional"))
    )
  )
)
